# 5_0_1.net
KiCad netlist of a schematic drawn in EasyEDA
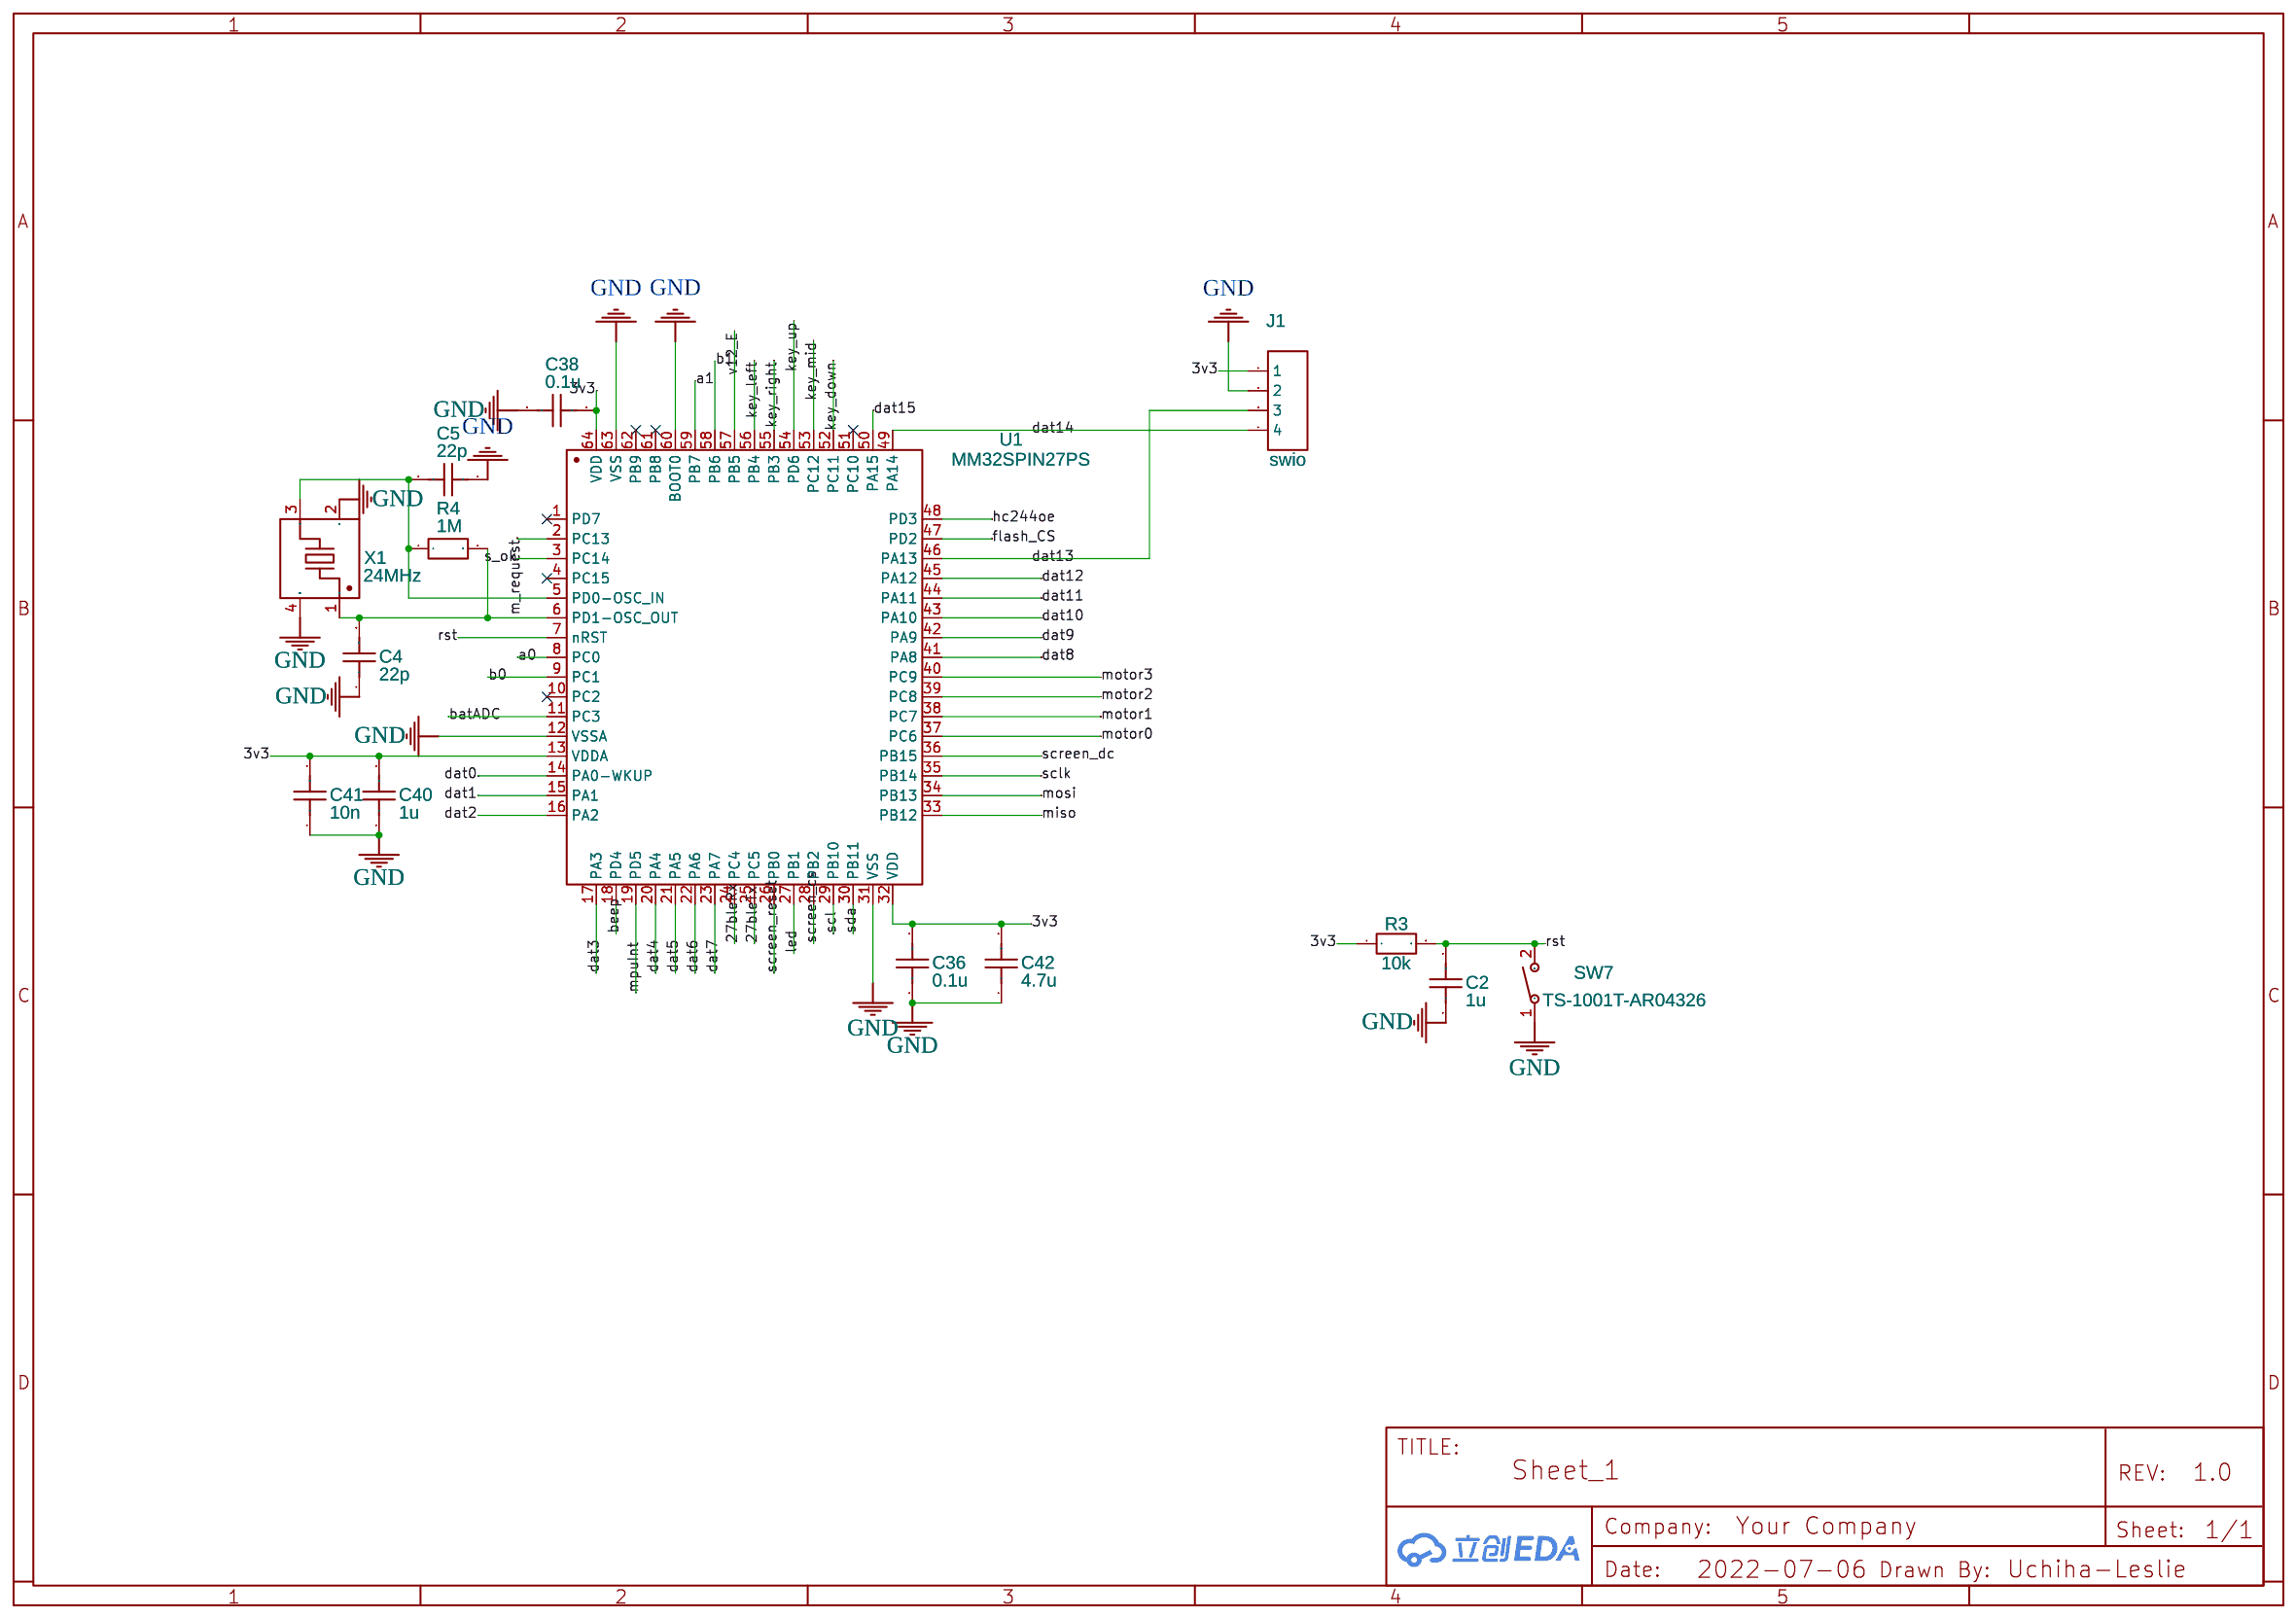
[diagram p0: spin27]
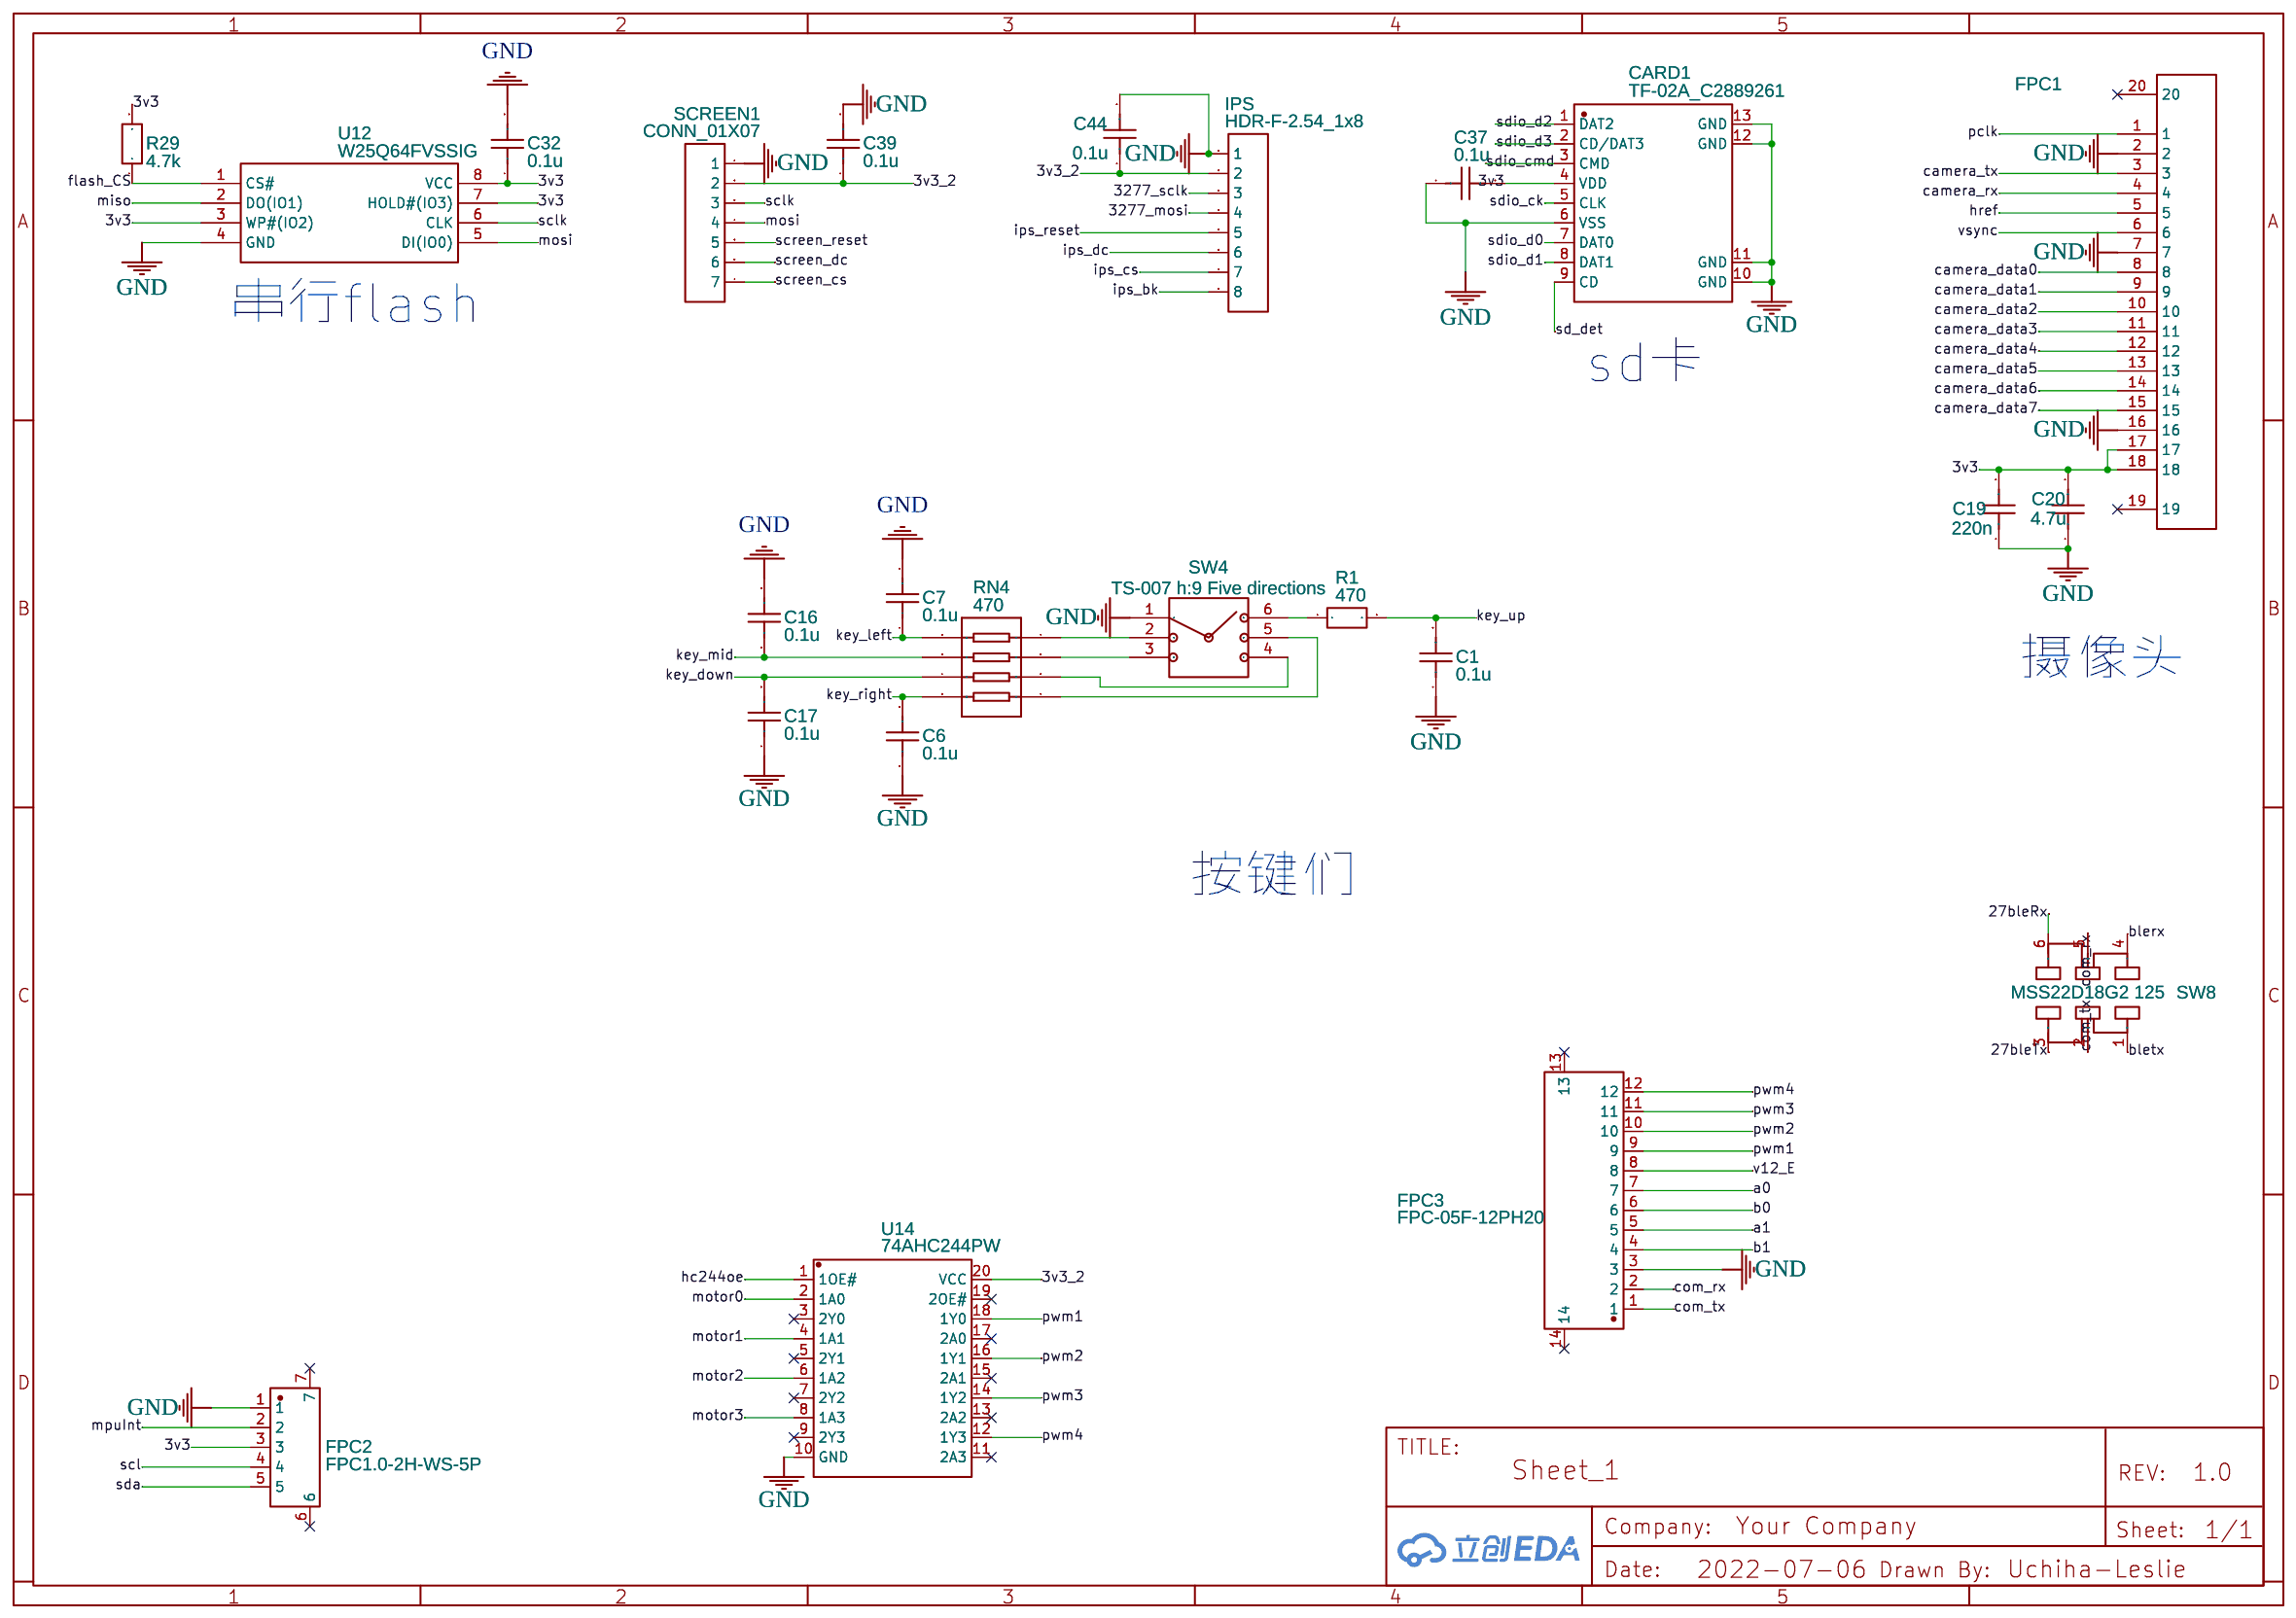
[diagram p1: 其他外设]
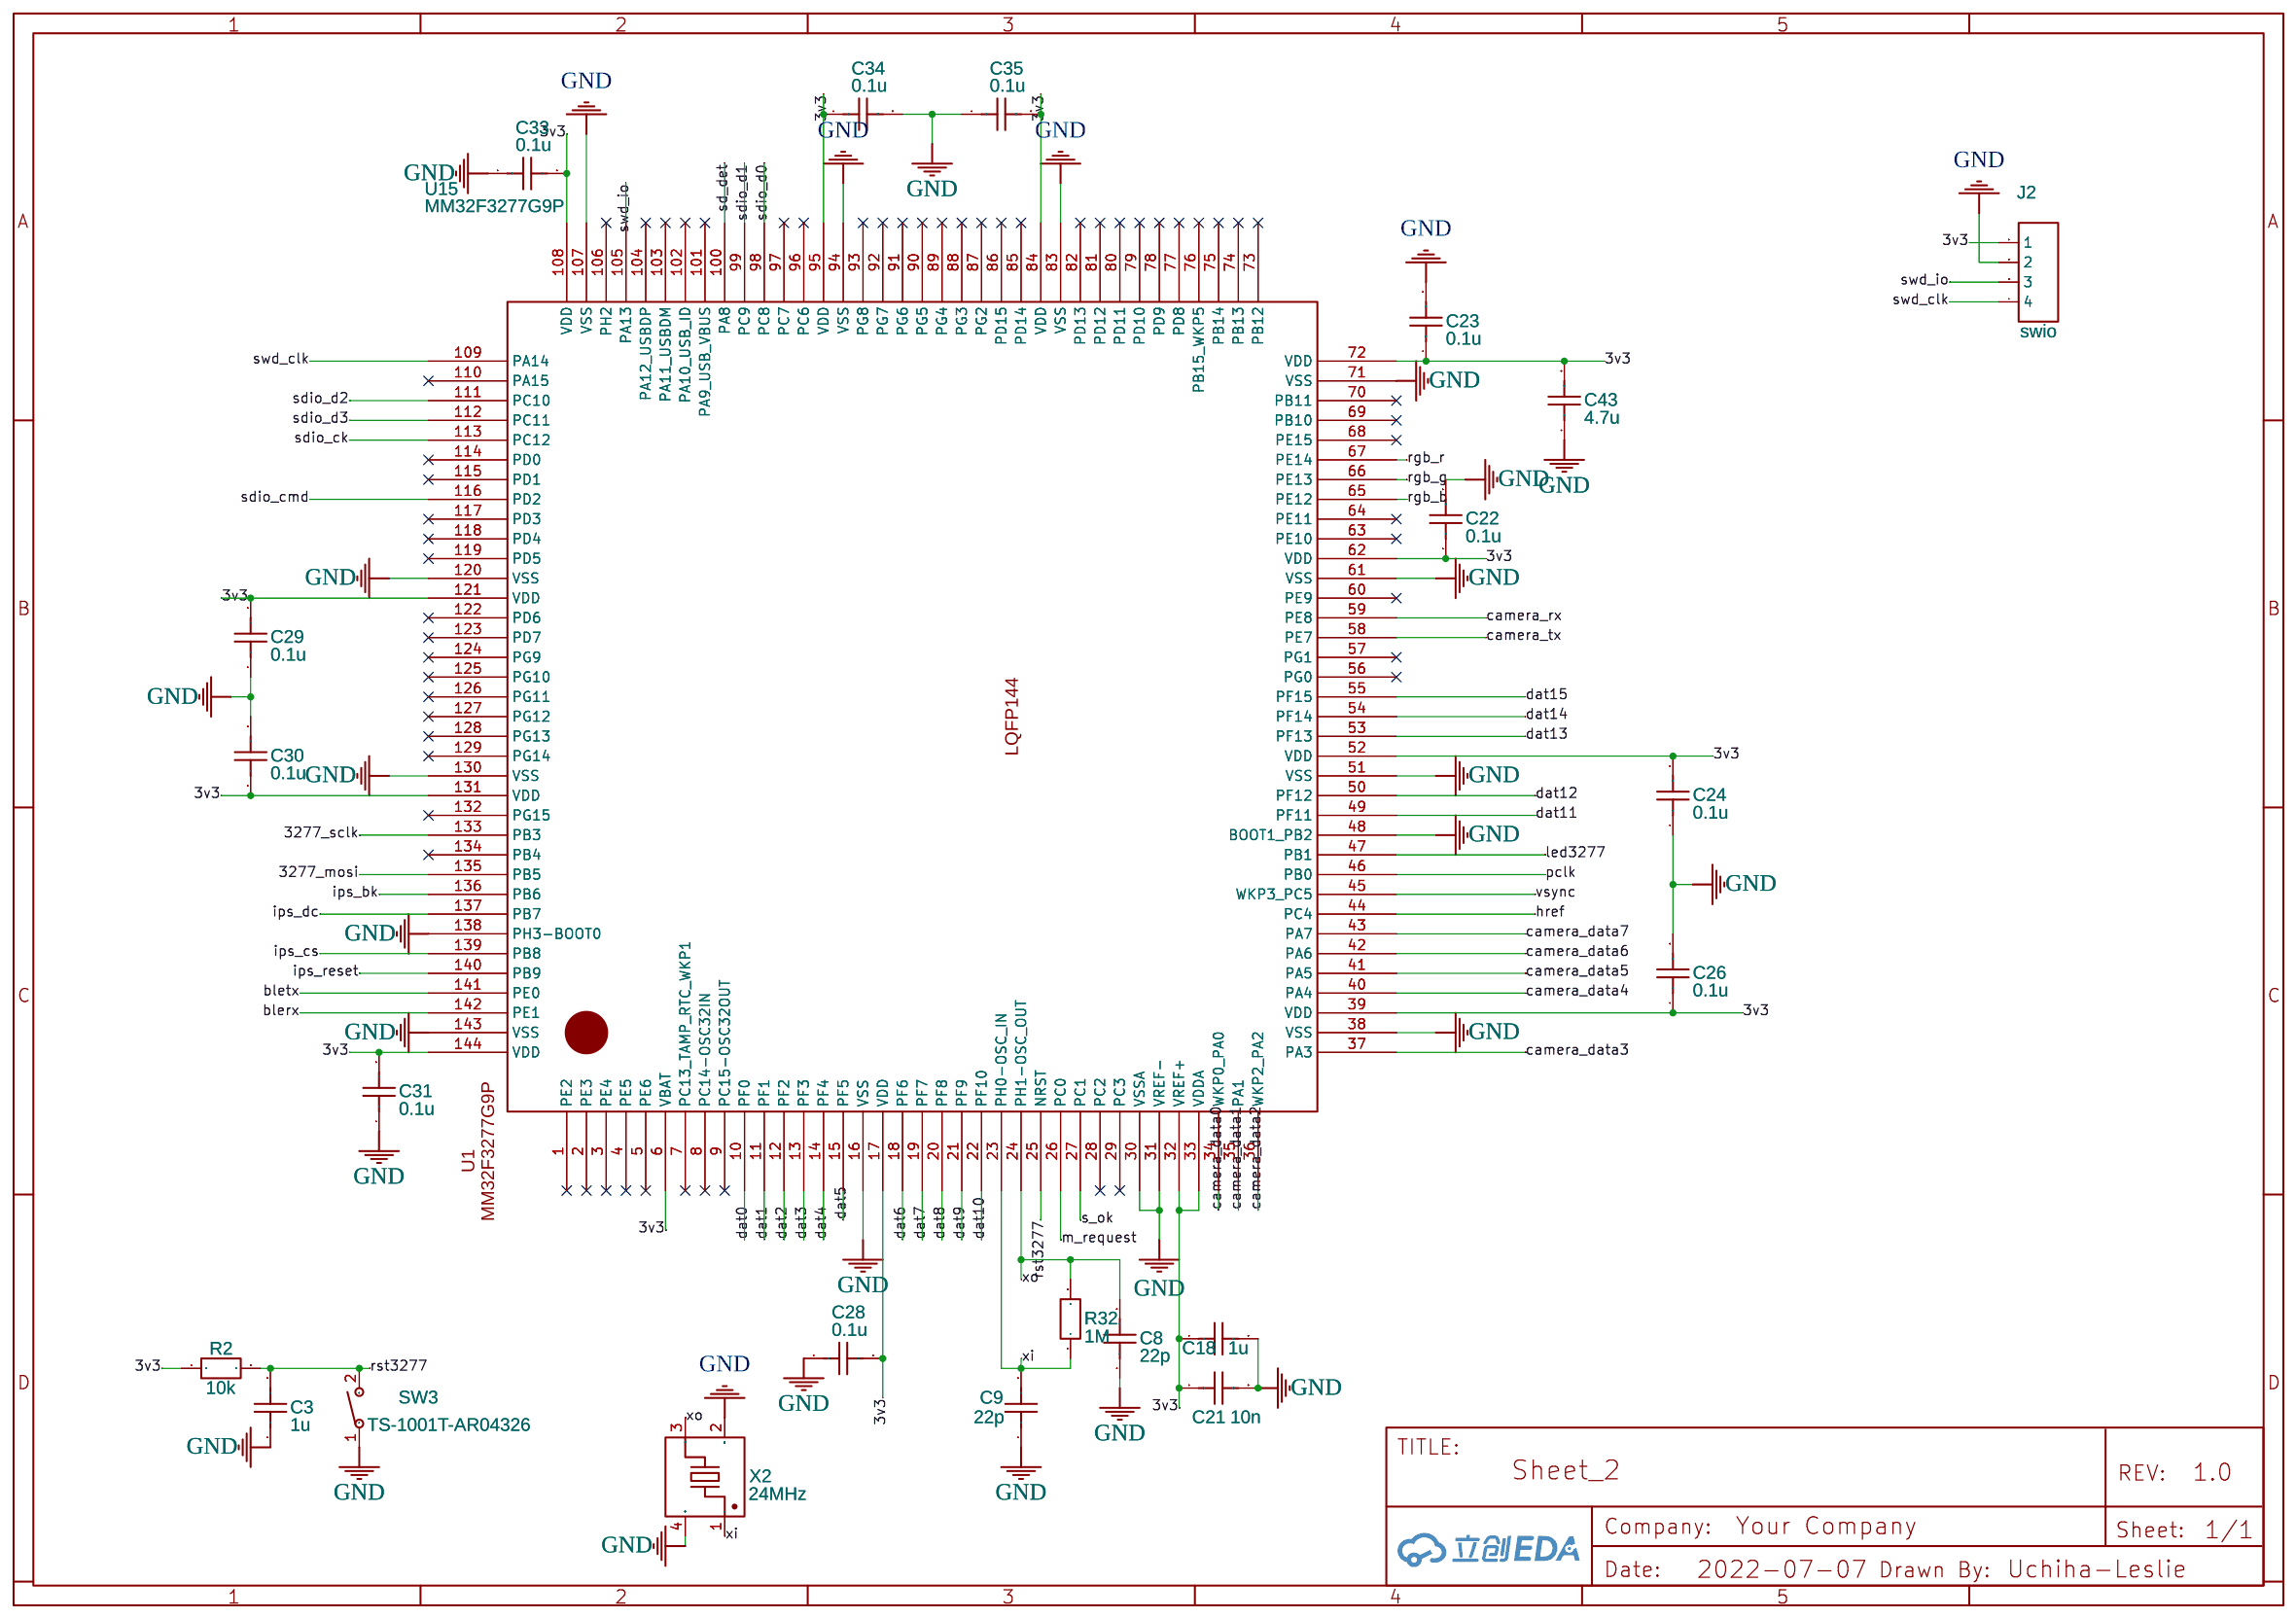
[diagram p2: 3277]
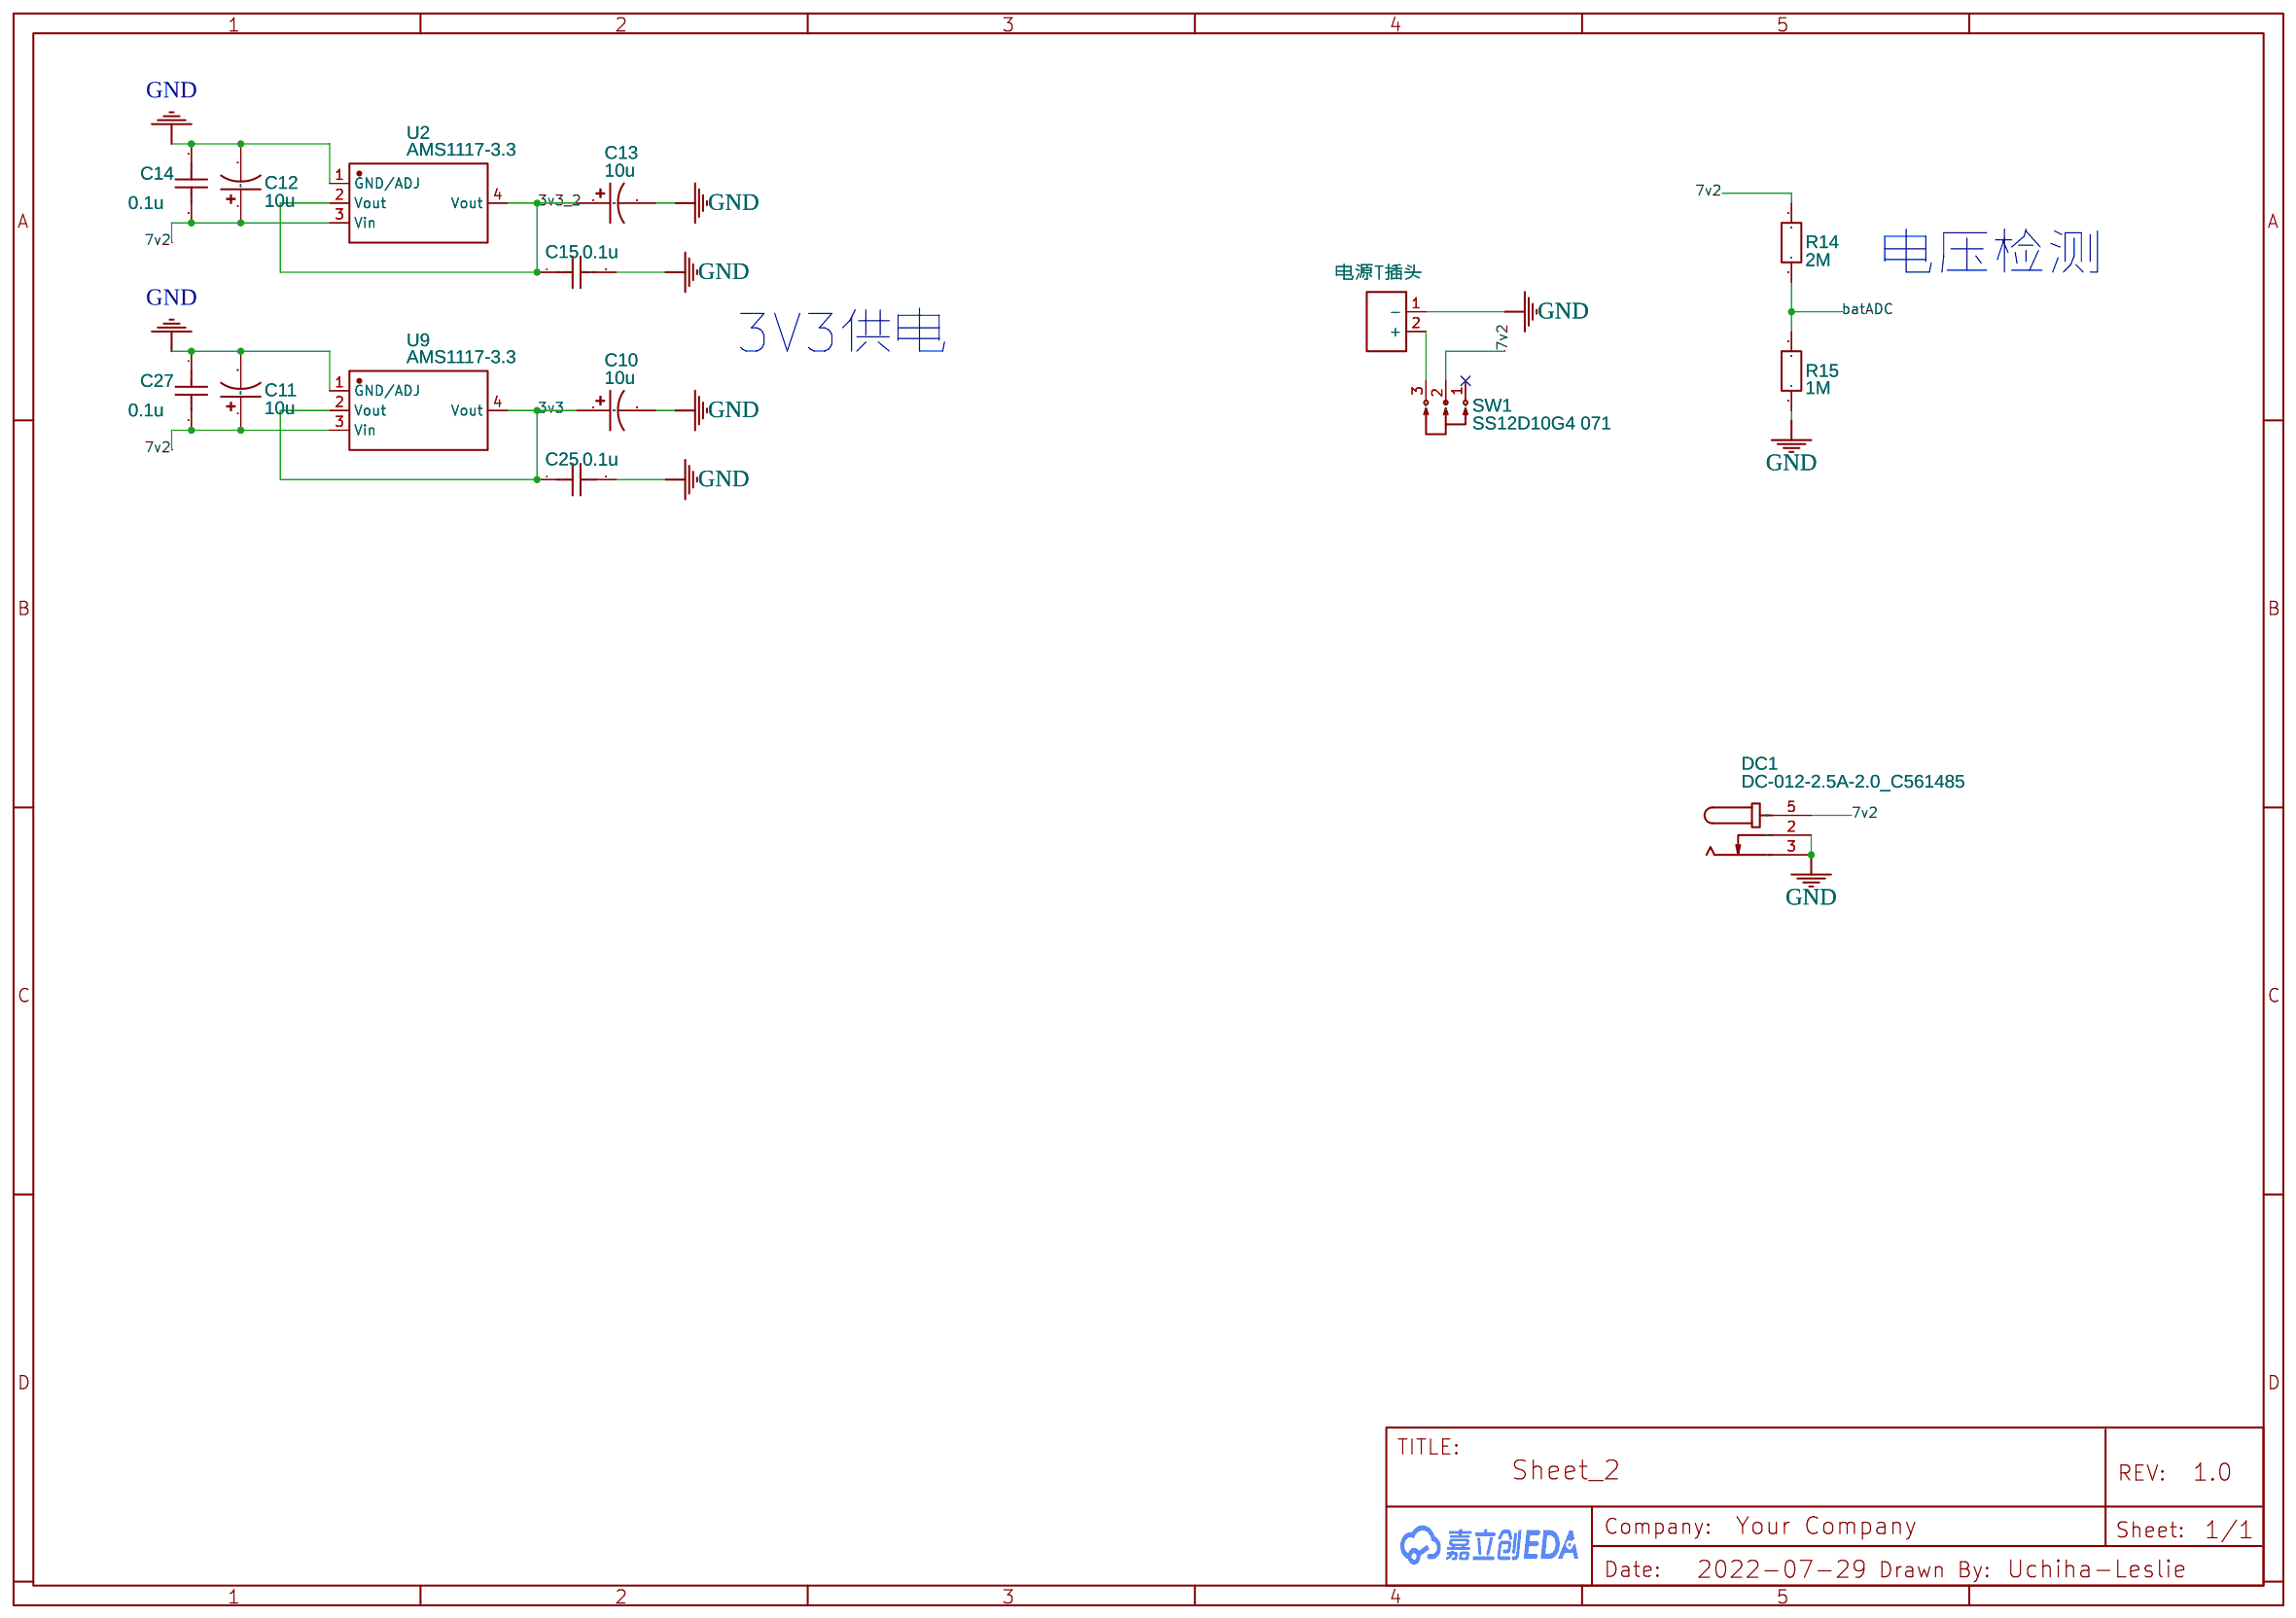
[diagram p3: 电源、稳压与测量]
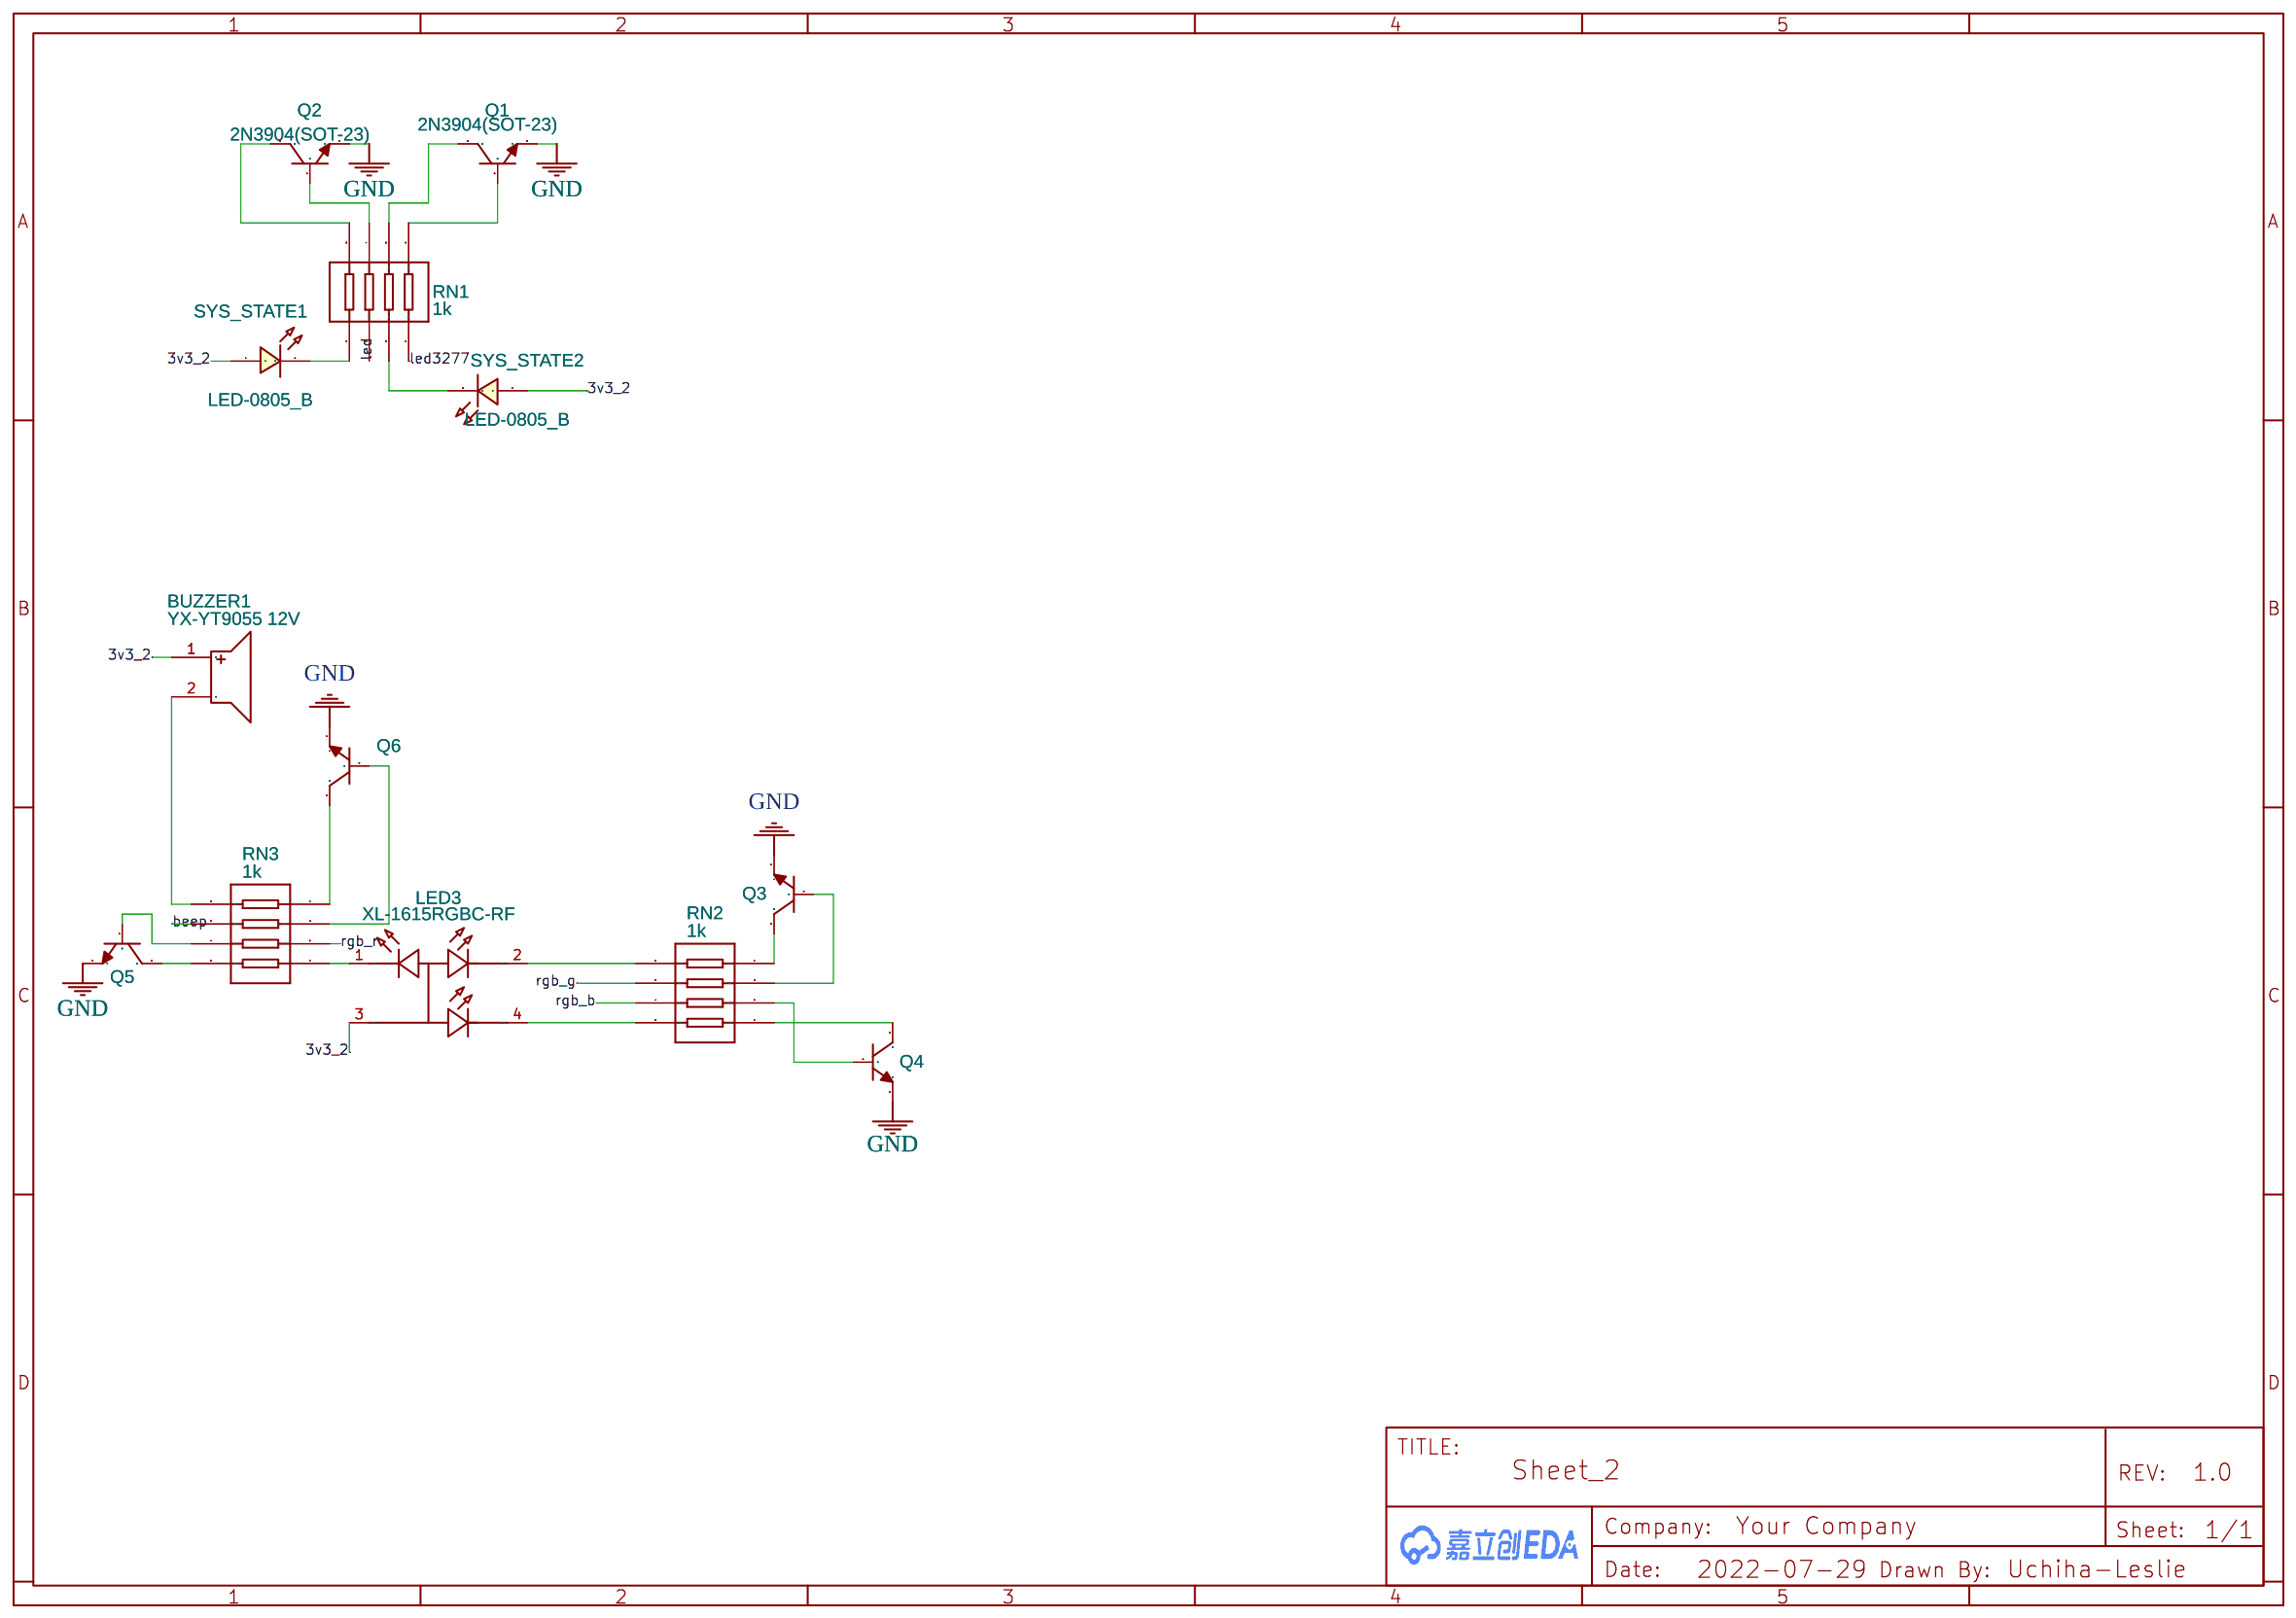
[diagram p4: 蜂鸣器与LED]

(export (version "E")
  (design (tool "Eeschema 10.0.6"))
  (components
    (comp (ref "C2") (value "1u") (libsource (lib "") (part "C_0603_US")))
    (comp (ref "C4") (value "22p") (libsource (lib "") (part "C_0603_US")))
    (comp (ref "C5") (value "22p") (libsource (lib "") (part "C_0603_US_1")))
    (comp (ref "C36") (value "0.1u") (libsource (lib "") (part "C_0402_US")))
    (comp (ref "C38") (value "0.1u") (libsource (lib "") (part "C_0402_US_1")))
    (comp (ref "C40") (value "1u") (libsource (lib "") (part "C_0603_US")))
    (comp (ref "C41") (value "10n") (libsource (lib "") (part "C_0603_US")))
    (comp (ref "C42") (value "4.7u") (libsource (lib "") (part "C_0603_US")))
    (comp (ref "J1")
      (value "swio")
      (fields (field (name "BOM_Supplier Part") "C124378"))
      (libsource (lib "") (part "HDR-M-2.54_1x4"))
    )
    (comp (ref "R3") (value "10k") (libsource (lib "") (part "R_0603_EU")))
    (comp (ref "R4") (value "1M") (libsource (lib "") (part "R_0603_EU")))
    (comp (ref "SW7")
      (value "TS-1001T-AR04326")
      (fields (field (name "BOM_Supplier Part") "C920203"))
      (libsource (lib "") (part "TS-1001T-AR04326"))
    )
    (comp (ref "U1")
      (value "MM32SPIN27PS")
      (fields
        (field (name "BOM_Manufacturer Part") "mm32spin27ps")
        (field (name "BOM_Supplier Part") "C2908053")
      )
      (libsource (lib "") (part "MM32SPIN27PS"))
    )
    (comp (ref "X1")
      (value "24MHz")
      (fields
        (field (name "BOM_Manufacturer Part") "CN4024M00012T8188012")
        (field (name "BOM_Supplier Part") "C708987")
      )
      (libsource (lib "") (part "CN4024M00012T8188012"))
    )
    (comp (ref "C1") (value "0.1u") (libsource (lib "") (part "C_0402_US")))
    (comp (ref "C6") (value "0.1u") (libsource (lib "") (part "C_0402_US")))
    (comp (ref "C7") (value "0.1u") (libsource (lib "") (part "C_0402_US")))
    (comp (ref "C16") (value "0.1u") (libsource (lib "") (part "C_0402_US")))
    (comp (ref "C17") (value "0.1u") (libsource (lib "") (part "C_0402_US")))
    (comp (ref "C19") (value "220n") (libsource (lib "") (part "C_0603_US")))
    (comp (ref "C20") (value "4.7u") (libsource (lib "") (part "C_0603_US")))
    (comp (ref "C32") (value "0.1u") (libsource (lib "") (part "C_0402_US")))
    (comp (ref "C37") (value "0.1u") (libsource (lib "") (part "C_0402_US_1")))
    (comp (ref "C39") (value "0.1u") (libsource (lib "") (part "C_0402_US")))
    (comp (ref "C44") (value "0.1u") (libsource (lib "") (part "C_0402_US")))
    (comp (ref "CARD1")
      (value "TF-02A_C2889261")
      (fields (field (name "BOM_Manufacturer Part") "TF-02A") (field (name "BOM_Supplier Part") "C2889261"))
      (libsource (lib "") (part "TF-02A_C2889261"))
    )
    (comp (ref "FPC1")
      (value "F0500WR-S-18PNLNG1GB0R")
      (fields (field (name "BOM_Supplier Part") "C247896"))
      (libsource (lib "") (part "F0500WR-S-18PNLNG1GB0R"))
    )
    (comp (ref "FPC2")
      (value "FPC1.0-2H-WS-5P")
      (fields (field (name "BOM_Supplier Part") "C9900003417"))
      (libsource (lib "") (part "FPC1.0-2H-WS-5P"))
    )
    (comp (ref "FPC3")
      (value "FPC-05F-12PH20")
      (fields (field (name "BOM_Supplier Part") "C2856799"))
      (libsource (lib "") (part "FPC-05F-12PH20"))
    )
    (comp (ref "IPS")
      (value "HDR-F-2.54_1x8")
      (fields (field (name "BOM_Supplier Part") "C225505"))
      (libsource (lib "") (part "HDR-F-2.54_1x8"))
    )
    (comp (ref "R1") (value "470") (libsource (lib "") (part "R_0603_EU")))
    (comp (ref "R29") (value "4.7k") (libsource (lib "") (part "R_0603_EU_1")))
    (comp (ref "RN4")
      (value "470")
      (fields
        (field (name "BOM_Manufacturer Part") "YC164-JR-070RL")
        (field (name "BOM_Supplier Part") "C327053")
      )
      (libsource (lib "") (part "YC164-JR-070RL"))
    )
    (comp (ref "SCREEN1") (value "CONN_01X07") (libsource (lib "") (part "CONN_01X07")))
    (comp (ref "SW4")
      (value "TS-007 h:9 Five directions")
      (fields (field (name "BOM_Supplier Part") "C3679"))
      (libsource (lib "") (part "TS-007 h{colon}9 Five directions"))
    )
    (comp (ref "SW8")
      (value "MSS22D18G2 125")
      (fields (field (name "BOM_Supplier Part") "C2906278"))
      (libsource (lib "") (part "MSS22D18G2 125"))
    )
    (comp (ref "U12")
      (value "W25Q64FVSSIG")
      (fields (field (name "BOM_Supplier Part") "C14067"))
      (libsource (lib "") (part "W25Q64FVSSIG"))
    )
    (comp (ref "U14")
      (value "74AHC244PW")
      (fields (field (name "BOM_Supplier Part") "C5515"))
      (libsource (lib "") (part "74AHC244PW"))
    )
    (comp (ref "C3") (value "1u") (libsource (lib "") (part "C_0603_US")))
    (comp (ref "C8") (value "22p") (libsource (lib "") (part "C_0603_US")))
    (comp (ref "C9") (value "22p") (libsource (lib "") (part "C_0603_US")))
    (comp (ref "C18") (value "1u") (libsource (lib "") (part "C_0603_US_1")))
    (comp (ref "C21") (value "10n") (libsource (lib "") (part "C_0603_US_1")))
    (comp (ref "C22") (value "0.1u") (libsource (lib "") (part "C_0402_US")))
    (comp (ref "C23") (value "0.1u") (libsource (lib "") (part "C_0402_US")))
    (comp (ref "C24") (value "0.1u") (libsource (lib "") (part "C_0402_US")))
    (comp (ref "C26") (value "0.1u") (libsource (lib "") (part "C_0402_US")))
    (comp (ref "C28") (value "0.1u") (libsource (lib "") (part "C_0402_US_1")))
    (comp (ref "C29") (value "0.1u") (libsource (lib "") (part "C_0402_US")))
    (comp (ref "C30") (value "0.1u") (libsource (lib "") (part "C_0402_US")))
    (comp (ref "C31") (value "0.1u") (libsource (lib "") (part "C_0402_US")))
    (comp (ref "C33") (value "0.1u") (libsource (lib "") (part "C_0402_US_1")))
    (comp (ref "C34") (value "0.1u") (libsource (lib "") (part "C_0402_US_1")))
    (comp (ref "C35") (value "0.1u") (libsource (lib "") (part "C_0402_US_1")))
    (comp (ref "C43") (value "4.7u") (libsource (lib "") (part "C_0603_US")))
    (comp (ref "J2")
      (value "swio")
      (fields (field (name "BOM_Supplier Part") "C124378"))
      (libsource (lib "") (part "HDR-M-2.54_1x4"))
    )
    (comp (ref "R2") (value "10k") (libsource (lib "") (part "R_0603_EU_1")))
    (comp (ref "R32") (value "1M") (libsource (lib "") (part "R_0603_EU")))
    (comp (ref "SW3")
      (value "TS-1001T-AR04326")
      (fields (field (name "BOM_Supplier Part") "C920203"))
      (libsource (lib "") (part "TS-1001T-AR04326"))
    )
    (comp (ref "U15") (value "MM32F3277G9P") (libsource (lib "") (part "MM32F3277G9P")))
    (comp (ref "X2")
      (value "24MHz")
      (fields
        (field (name "BOM_Manufacturer Part") "CN4024M00012T8188012")
        (field (name "BOM_Supplier Part") "C708987")
      )
      (libsource (lib "") (part "CN4024M00012T8188012"))
    )
    (comp (ref "C10") (value "10u") (libsource (lib "") (part "C_Tan_SMD_A_US")))
    (comp (ref "C11") (value "10u") (libsource (lib "") (part "C_Tan_SMD_A_US_1")))
    (comp (ref "C12") (value "10u") (libsource (lib "") (part "C_Tan_SMD_A_US_1")))
    (comp (ref "C13") (value "10u") (libsource (lib "") (part "C_Tan_SMD_A_US")))
    (comp (ref "C14") (value "0.1u") (libsource (lib "") (part "C_0603_US_1")))
    (comp (ref "C15") (value "0.1u") (libsource (lib "") (part "C_0603_US")))
    (comp (ref "C25") (value "0.1u") (libsource (lib "") (part "C_0603_US")))
    (comp (ref "C27") (value "0.1u") (libsource (lib "") (part "C_0603_US_1")))
    (comp (ref "DC1")
      (value "DC-012-2.5A-2.0_C561485")
      (fields
        (field (name "BOM_Manufacturer Part") "DC-012-2.5A-2.0")
        (field (name "BOM_Supplier Part") "C561485")
      )
      (libsource (lib "") (part "DC-012-2.5A-2.0_C561485"))
    )
    (comp (ref "H1")
      (value "电源T插头")
      (fields (field (name "BOM_Manufacturer Part") "3-644456-2") (field (name "BOM_Supplier Part") "C90288"))
      (libsource (lib "") (part "电源T插头"))
    )
    (comp (ref "R14") (value "2M") (libsource (lib "") (part "R_0603_EU")))
    (comp (ref "R15") (value "1M") (libsource (lib "") (part "R_0603_EU")))
    (comp (ref "SW1")
      (value "SS12D10G4 071")
      (fields (field (name "BOM_Supplier Part") "C2887259"))
      (libsource (lib "") (part "SS12D10G4 071"))
    )
    (comp (ref "U2")
      (value "AMS1117-3.3")
      (fields (field (name "BOM_Supplier Part") "C6186"))
      (libsource (lib "") (part "AMS1117-3.3"))
    )
    (comp (ref "U9")
      (value "AMS1117-3.3")
      (fields (field (name "BOM_Supplier Part") "C6186"))
      (libsource (lib "") (part "AMS1117-3.3"))
    )
    (comp (ref "BUZZER1")
      (value "YX-YT9055 12V")
      (fields (field (name "BOM_Supplier Part") "C781852"))
      (libsource (lib "") (part "YX-YT9055 12V"))
    )
    (comp (ref "LED3")
      (value "XL-1615RGBC-RF")
      (fields (field (name "BOM_Supplier Part") "C965840"))
      (libsource (lib "") (part "XL-1615RGBC-RF"))
    )
    (comp (ref "Q1")
      (value "2N3904(SOT-23)")
      (fields
        (field (name "BOM_Manufacturer Part") "2n3904S-RTK/PS")
        (field (name "BOM_Supplier Part") "C18536")
      )
      (libsource (lib "") (part "2N3904(SOT-23)_1"))
    )
    (comp (ref "Q2")
      (value "2N3904(SOT-23)")
      (fields
        (field (name "BOM_Manufacturer Part") "2n3904S-RTK/PS")
        (field (name "BOM_Supplier Part") "C18536")
      )
      (libsource (lib "") (part "2N3904(SOT-23)_1"))
    )
    (comp (ref "Q3")
      (value "2N3904(SOT-23)")
      (fields
        (field (name "BOM_Manufacturer Part") "2n3904S-RTK/PS")
        (field (name "BOM_Supplier Part") "C18536")
      )
      (libsource (lib "") (part "2N3904(SOT-23)"))
    )
    (comp (ref "Q4")
      (value "2N3904(SOT-23)")
      (fields
        (field (name "BOM_Manufacturer Part") "2n3904S-RTK/PS")
        (field (name "BOM_Supplier Part") "C18536")
      )
      (libsource (lib "") (part "2N3904(SOT-23)_2"))
    )
    (comp (ref "Q5")
      (value "2N3904(SOT-23)")
      (fields
        (field (name "BOM_Manufacturer Part") "2n3904S-RTK/PS")
        (field (name "BOM_Supplier Part") "C18536")
      )
      (libsource (lib "") (part "2N3904(SOT-23)_3"))
    )
    (comp (ref "Q6")
      (value "2N3904(SOT-23)")
      (fields
        (field (name "BOM_Manufacturer Part") "2n3904S-RTK/PS")
        (field (name "BOM_Supplier Part") "C18536")
      )
      (libsource (lib "") (part "2N3904(SOT-23)"))
    )
    (comp (ref "RN1")
      (value "1k")
      (fields
        (field (name "BOM_Manufacturer Part") "YC164-JR-070RL")
        (field (name "BOM_Supplier Part") "C327053")
      )
      (libsource (lib "") (part "YC164-JR-070RL"))
    )
    (comp (ref "RN2")
      (value "1k")
      (fields
        (field (name "BOM_Manufacturer Part") "YC164-JR-070RL")
        (field (name "BOM_Supplier Part") "C327053")
      )
      (libsource (lib "") (part "YC164-JR-070RL_1"))
    )
    (comp (ref "RN3")
      (value "1k")
      (fields
        (field (name "BOM_Manufacturer Part") "YC164-JR-070RL")
        (field (name "BOM_Supplier Part") "C327053")
      )
      (libsource (lib "") (part "YC164-JR-070RL_1"))
    )
    (comp (ref "SYS_STATE1")
      (value "LED-0805_B")
      (fields
        (field (name "BOM_Manufacturer Part") "D-B080508B1-KS2")
        (field (name "BOM_Supplier Part") "C108412")
      )
      (libsource (lib "") (part "LED-0805_B"))
    )
    (comp (ref "SYS_STATE2")
      (value "LED-0805_B")
      (fields
        (field (name "BOM_Manufacturer Part") "D-B080508B1-KS2")
        (field (name "BOM_Supplier Part") "C108412")
      )
      (libsource (lib "") (part "LED-0805_B_1"))
    )
  )
  (nets
    (net (code "1") (name "3v3") (class "Default")
      (node (ref "C10") (pin "1") (pinfunction "1_1") (pintype "unspecified"))
      (node (ref "C18") (pin "1") (pinfunction "1_1") (pintype "unspecified"))
      (node (ref "C19") (pin "2") (pinfunction "2_2") (pintype "unspecified"))
      (node (ref "C20") (pin "2") (pinfunction "2_2") (pintype "unspecified"))
      (node (ref "C21") (pin "1") (pinfunction "1_1") (pintype "unspecified"))
      (node (ref "C22") (pin "1") (pinfunction "1_1") (pintype "unspecified"))
      (node (ref "C23") (pin "1") (pinfunction "1_1") (pintype "unspecified"))
      (node (ref "C24") (pin "2") (pinfunction "2_2") (pintype "unspecified"))
      (node (ref "C25") (pin "1") (pinfunction "1_1") (pintype "unspecified"))
      (node (ref "C26") (pin "1") (pinfunction "1_1") (pintype "unspecified"))
      (node (ref "C28") (pin "2") (pinfunction "2_2") (pintype "unspecified"))
      (node (ref "C29") (pin "2") (pinfunction "2_2") (pintype "unspecified"))
      (node (ref "C30") (pin "1") (pinfunction "1_1") (pintype "unspecified"))
      (node (ref "C31") (pin "2") (pinfunction "2_2") (pintype "unspecified"))
      (node (ref "C32") (pin "1") (pinfunction "1_1") (pintype "unspecified"))
      (node (ref "C33") (pin "2") (pinfunction "2_2") (pintype "unspecified"))
      (node (ref "C34") (pin "1") (pinfunction "1_1") (pintype "unspecified"))
      (node (ref "C35") (pin "2") (pinfunction "2_2") (pintype "unspecified"))
      (node (ref "C36") (pin "2") (pinfunction "2_2") (pintype "unspecified"))
      (node (ref "C37") (pin "2") (pinfunction "2_2") (pintype "unspecified"))
      (node (ref "C38") (pin "2") (pinfunction "2_2") (pintype "unspecified"))
      (node (ref "C40") (pin "2") (pinfunction "2_2") (pintype "unspecified"))
      (node (ref "C41") (pin "2") (pinfunction "2_2") (pintype "unspecified"))
      (node (ref "C42") (pin "2") (pinfunction "2_2") (pintype "unspecified"))
      (node (ref "C43") (pin "2") (pinfunction "2_2") (pintype "unspecified"))
      (node (ref "CARD1") (pin "4") (pinfunction "VDD_4") (pintype "unspecified"))
      (node (ref "FPC1") (pin "17") (pinfunction "17_17") (pintype "unspecified"))
      (node (ref "FPC1") (pin "18") (pinfunction "18_18") (pintype "unspecified"))
      (node (ref "FPC2") (pin "3") (pinfunction "3_3") (pintype "unspecified"))
      (node (ref "J1") (pin "1") (pinfunction "1_1") (pintype "unspecified"))
      (node (ref "J2") (pin "1") (pinfunction "1_1") (pintype "unspecified"))
      (node (ref "R2") (pin "1") (pinfunction "1_1") (pintype "unspecified"))
      (node (ref "R29") (pin "2") (pinfunction "2_2") (pintype "unspecified"))
      (node (ref "R3") (pin "1") (pinfunction "1_1") (pintype "unspecified"))
      (node (ref "U1") (pin "13") (pinfunction "VDDA_13") (pintype "unspecified"))
      (node (ref "U1") (pin "32") (pinfunction "VDD_32") (pintype "unspecified"))
      (node (ref "U1") (pin "64") (pinfunction "VDD_64") (pintype "unspecified"))
      (node (ref "U12") (pin "3") (pinfunction "WP#(IO2)_3") (pintype "unspecified"))
      (node (ref "U12") (pin "7") (pinfunction "HOLD#(IO3)_7") (pintype "unspecified"))
      (node (ref "U12") (pin "8") (pinfunction "VCC_8") (pintype "unspecified"))
      (node (ref "U15") (pin "108") (pinfunction "VDD_108") (pintype "unspecified"))
      (node (ref "U15") (pin "121") (pinfunction "VDD_121") (pintype "unspecified"))
      (node (ref "U15") (pin "131") (pinfunction "VDD_131") (pintype "unspecified"))
      (node (ref "U15") (pin "144") (pinfunction "VDD_144") (pintype "unspecified"))
      (node (ref "U15") (pin "17") (pinfunction "VDD_17") (pintype "unspecified"))
      (node (ref "U15") (pin "32") (pinfunction "VREF+_32") (pintype "unspecified"))
      (node (ref "U15") (pin "33") (pinfunction "VDDA_33") (pintype "unspecified"))
      (node (ref "U15") (pin "39") (pinfunction "VDD_39") (pintype "unspecified"))
      (node (ref "U15") (pin "52") (pinfunction "VDD_52") (pintype "unspecified"))
      (node (ref "U15") (pin "6") (pinfunction "VBAT_6") (pintype "unspecified"))
      (node (ref "U15") (pin "62") (pinfunction "VDD_62") (pintype "unspecified"))
      (node (ref "U15") (pin "72") (pinfunction "VDD_72") (pintype "unspecified"))
      (node (ref "U15") (pin "84") (pinfunction "VDD_84") (pintype "unspecified"))
      (node (ref "U15") (pin "95") (pinfunction "VDD_95") (pintype "unspecified"))
      (node (ref "U9") (pin "2") (pinfunction "Vout_2") (pintype "unspecified"))
      (node (ref "U9") (pin "4") (pinfunction "Vout_4") (pintype "unspecified"))
    )
    (net (code "2") (name "3v3_2") (class "Default")
      (node (ref "BUZZER1") (pin "1") (pinfunction "1_1") (pintype "unspecified"))
      (node (ref "C13") (pin "1") (pinfunction "1_1") (pintype "unspecified"))
      (node (ref "C15") (pin "1") (pinfunction "1_1") (pintype "unspecified"))
      (node (ref "C39") (pin "1") (pinfunction "1_1") (pintype "unspecified"))
      (node (ref "C44") (pin "1") (pinfunction "1_1") (pintype "unspecified"))
      (node (ref "IPS") (pin "2") (pinfunction "2_2") (pintype "unspecified"))
      (node (ref "LED3") (pin "3") (pinfunction "COM+_3") (pintype "unspecified"))
      (node (ref "SCREEN1") (pin "2") (pinfunction "2_2") (pintype "input"))
      (node (ref "SYS_STATE1") (pin "1") (pinfunction "1_1") (pintype "unspecified"))
      (node (ref "SYS_STATE2") (pin "1") (pinfunction "1_1") (pintype "unspecified"))
      (node (ref "U14") (pin "20") (pinfunction "VCC_20") (pintype "unspecified"))
      (node (ref "U2") (pin "2") (pinfunction "Vout_2") (pintype "unspecified"))
      (node (ref "U2") (pin "4") (pinfunction "Vout_4") (pintype "unspecified"))
    )
    (net (code "3") (name "7v2") (class "Default")
      (node (ref "C11") (pin "1") (pinfunction "1_1") (pintype "unspecified"))
      (node (ref "C12") (pin "1") (pinfunction "1_1") (pintype "unspecified"))
      (node (ref "C14") (pin "2") (pinfunction "2_2") (pintype "unspecified"))
      (node (ref "C27") (pin "2") (pinfunction "2_2") (pintype "unspecified"))
      (node (ref "DC1") (pin "5") (pinfunction "5_5") (pintype "unspecified"))
      (node (ref "R14") (pin "2") (pinfunction "2_2") (pintype "unspecified"))
      (node (ref "SW1") (pin "2") (pinfunction "2_2") (pintype "unspecified"))
      (node (ref "U2") (pin "3") (pinfunction "Vin_3") (pintype "unspecified"))
      (node (ref "U9") (pin "3") (pinfunction "Vin_3") (pintype "unspecified"))
    )
    (net (code "4") (name "27bleRx") (class "Default")
      (node (ref "SW8") (pin "6") (pinfunction "6_6") (pintype "unspecified"))
      (node (ref "U1") (pin "24") (pinfunction "PC4_24") (pintype "unspecified"))
    )
    (net (code "5") (name "27bleTx") (class "Default")
      (node (ref "SW8") (pin "3") (pinfunction "3_3") (pintype "unspecified"))
      (node (ref "U1") (pin "25") (pinfunction "PC5_25") (pintype "unspecified"))
    )
    (net (code "6") (name "3277_mosi") (class "Default")
      (node (ref "IPS") (pin "4") (pinfunction "4_4") (pintype "unspecified"))
      (node (ref "U15") (pin "135") (pinfunction "PB5_135") (pintype "unspecified"))
    )
    (net (code "7") (name "3277_sclk") (class "Default")
      (node (ref "IPS") (pin "3") (pinfunction "3_3") (pintype "unspecified"))
      (node (ref "U15") (pin "133") (pinfunction "PB3_133") (pintype "unspecified"))
    )
    (net (code "8") (name "GND") (class "Default")
      (node (ref "C1") (pin "1") (pinfunction "1_1") (pintype "unspecified"))
      (node (ref "C10") (pin "2") (pinfunction "2_2") (pintype "unspecified"))
      (node (ref "C11") (pin "2") (pinfunction "2_2") (pintype "unspecified"))
      (node (ref "C12") (pin "2") (pinfunction "2_2") (pintype "unspecified"))
      (node (ref "C13") (pin "2") (pinfunction "2_2") (pintype "unspecified"))
      (node (ref "C14") (pin "1") (pinfunction "1_1") (pintype "unspecified"))
      (node (ref "C15") (pin "2") (pinfunction "2_2") (pintype "unspecified"))
      (node (ref "C16") (pin "2") (pinfunction "2_2") (pintype "unspecified"))
      (node (ref "C17") (pin "1") (pinfunction "1_1") (pintype "unspecified"))
      (node (ref "C18") (pin "2") (pinfunction "2_2") (pintype "unspecified"))
      (node (ref "C19") (pin "1") (pinfunction "1_1") (pintype "unspecified"))
      (node (ref "C2") (pin "1") (pinfunction "1_1") (pintype "unspecified"))
      (node (ref "C20") (pin "1") (pinfunction "1_1") (pintype "unspecified"))
      (node (ref "C21") (pin "2") (pinfunction "2_2") (pintype "unspecified"))
      (node (ref "C22") (pin "2") (pinfunction "2_2") (pintype "unspecified"))
      (node (ref "C23") (pin "2") (pinfunction "2_2") (pintype "unspecified"))
      (node (ref "C24") (pin "1") (pinfunction "1_1") (pintype "unspecified"))
      (node (ref "C25") (pin "2") (pinfunction "2_2") (pintype "unspecified"))
      (node (ref "C26") (pin "2") (pinfunction "2_2") (pintype "unspecified"))
      (node (ref "C27") (pin "1") (pinfunction "1_1") (pintype "unspecified"))
      (node (ref "C28") (pin "1") (pinfunction "1_1") (pintype "unspecified"))
      (node (ref "C29") (pin "1") (pinfunction "1_1") (pintype "unspecified"))
      (node (ref "C3") (pin "1") (pinfunction "1_1") (pintype "unspecified"))
      (node (ref "C30") (pin "2") (pinfunction "2_2") (pintype "unspecified"))
      (node (ref "C31") (pin "1") (pinfunction "1_1") (pintype "unspecified"))
      (node (ref "C32") (pin "2") (pinfunction "2_2") (pintype "unspecified"))
      (node (ref "C33") (pin "1") (pinfunction "1_1") (pintype "unspecified"))
      (node (ref "C34") (pin "2") (pinfunction "2_2") (pintype "unspecified"))
      (node (ref "C35") (pin "1") (pinfunction "1_1") (pintype "unspecified"))
      (node (ref "C36") (pin "1") (pinfunction "1_1") (pintype "unspecified"))
      (node (ref "C37") (pin "1") (pinfunction "1_1") (pintype "unspecified"))
      (node (ref "C38") (pin "1") (pinfunction "1_1") (pintype "unspecified"))
      (node (ref "C39") (pin "2") (pinfunction "2_2") (pintype "unspecified"))
      (node (ref "C4") (pin "1") (pinfunction "1_1") (pintype "unspecified"))
      (node (ref "C40") (pin "1") (pinfunction "1_1") (pintype "unspecified"))
      (node (ref "C41") (pin "1") (pinfunction "1_1") (pintype "unspecified"))
      (node (ref "C42") (pin "1") (pinfunction "1_1") (pintype "unspecified"))
      (node (ref "C43") (pin "1") (pinfunction "1_1") (pintype "unspecified"))
      (node (ref "C44") (pin "2") (pinfunction "2_2") (pintype "unspecified"))
      (node (ref "C5") (pin "1") (pinfunction "1_1") (pintype "unspecified"))
      (node (ref "C6") (pin "1") (pinfunction "1_1") (pintype "unspecified"))
      (node (ref "C7") (pin "2") (pinfunction "2_2") (pintype "unspecified"))
      (node (ref "C8") (pin "1") (pinfunction "1_1") (pintype "unspecified"))
      (node (ref "C9") (pin "1") (pinfunction "1_1") (pintype "unspecified"))
      (node (ref "CARD1") (pin "10") (pinfunction "GND_10") (pintype "unspecified"))
      (node (ref "CARD1") (pin "11") (pinfunction "GND_11") (pintype "unspecified"))
      (node (ref "CARD1") (pin "12") (pinfunction "GND_12") (pintype "unspecified"))
      (node (ref "CARD1") (pin "13") (pinfunction "GND_13") (pintype "unspecified"))
      (node (ref "CARD1") (pin "6") (pinfunction "VSS_6") (pintype "unspecified"))
      (node (ref "DC1") (pin "2") (pinfunction "2_2") (pintype "unspecified"))
      (node (ref "DC1") (pin "3") (pinfunction "3_3") (pintype "unspecified"))
      (node (ref "FPC1") (pin "16") (pinfunction "16_16") (pintype "unspecified"))
      (node (ref "FPC1") (pin "2") (pinfunction "2_2") (pintype "unspecified"))
      (node (ref "FPC1") (pin "7") (pinfunction "7_7") (pintype "unspecified"))
      (node (ref "FPC2") (pin "1") (pinfunction "1_1") (pintype "unspecified"))
      (node (ref "FPC3") (pin "3") (pinfunction "3_3") (pintype "unspecified"))
      (node (ref "H1") (pin "1") (pinfunction "-_1") (pintype "unspecified"))
      (node (ref "IPS") (pin "1") (pinfunction "1_1") (pintype "unspecified"))
      (node (ref "J1") (pin "2") (pinfunction "2_2") (pintype "unspecified"))
      (node (ref "J2") (pin "2") (pinfunction "2_2") (pintype "unspecified"))
      (node (ref "Q1") (pin "1") (pinfunction "E_1") (pintype "input"))
      (node (ref "Q2") (pin "1") (pinfunction "E_1") (pintype "input"))
      (node (ref "Q3") (pin "1") (pinfunction "E_1") (pintype "input"))
      (node (ref "Q4") (pin "1") (pinfunction "E_1") (pintype "input"))
      (node (ref "Q5") (pin "1") (pinfunction "E_1") (pintype "input"))
      (node (ref "Q6") (pin "1") (pinfunction "E_1") (pintype "input"))
      (node (ref "R15") (pin "1") (pinfunction "1_1") (pintype "unspecified"))
      (node (ref "SCREEN1") (pin "1") (pinfunction "1_1") (pintype "input"))
      (node (ref "SW3") (pin "1") (pinfunction "1_1") (pintype "unspecified"))
      (node (ref "SW4") (pin "1") (pinfunction "1_1") (pintype "input"))
      (node (ref "SW7") (pin "1") (pinfunction "1_1") (pintype "unspecified"))
      (node (ref "U1") (pin "12") (pinfunction "VSSA_12") (pintype "unspecified"))
      (node (ref "U1") (pin "31") (pinfunction "VSS_31") (pintype "unspecified"))
      (node (ref "U1") (pin "60") (pinfunction "BOOT0_60") (pintype "unspecified"))
      (node (ref "U1") (pin "63") (pinfunction "VSS_63") (pintype "unspecified"))
      (node (ref "U12") (pin "4") (pinfunction "GND_4") (pintype "unspecified"))
      (node (ref "U14") (pin "10") (pinfunction "GND_10") (pintype "unspecified"))
      (node (ref "U15") (pin "107") (pinfunction "VSS_107") (pintype "unspecified"))
      (node (ref "U15") (pin "120") (pinfunction "VSS_120") (pintype "unspecified"))
      (node (ref "U15") (pin "130") (pinfunction "VSS_130") (pintype "unspecified"))
      (node (ref "U15") (pin "138") (pinfunction "PH3-BOOT0_138") (pintype "unspecified"))
      (node (ref "U15") (pin "143") (pinfunction "VSS_143") (pintype "unspecified"))
      (node (ref "U15") (pin "16") (pinfunction "VSS_16") (pintype "unspecified"))
      (node (ref "U15") (pin "30") (pinfunction "VSSA_30") (pintype "unspecified"))
      (node (ref "U15") (pin "31") (pinfunction "VREF-_31") (pintype "unspecified"))
      (node (ref "U15") (pin "38") (pinfunction "VSS_38") (pintype "unspecified"))
      (node (ref "U15") (pin "48") (pinfunction "BOOT1_PB2_48") (pintype "unspecified"))
      (node (ref "U15") (pin "51") (pinfunction "VSS_51") (pintype "unspecified"))
      (node (ref "U15") (pin "61") (pinfunction "VSS_61") (pintype "unspecified"))
      (node (ref "U15") (pin "71") (pinfunction "VSS_71") (pintype "unspecified"))
      (node (ref "U15") (pin "83") (pinfunction "VSS_83") (pintype "unspecified"))
      (node (ref "U15") (pin "94") (pinfunction "VSS_94") (pintype "unspecified"))
      (node (ref "U2") (pin "1") (pinfunction "GND/ADJ_1") (pintype "unspecified"))
      (node (ref "U9") (pin "1") (pinfunction "GND/ADJ_1") (pintype "unspecified"))
      (node (ref "X1") (pin "2") (pinfunction "GND_2") (pintype "input"))
      (node (ref "X1") (pin "4") (pinfunction "GND_4") (pintype "input"))
      (node (ref "X2") (pin "2") (pinfunction "GND_2") (pintype "input"))
      (node (ref "X2") (pin "4") (pinfunction "GND_4") (pintype "input"))
    )
    (net (code "9") (name "Net-(BUZZER1-Pad2)") (class "Default")
      (node (ref "BUZZER1") (pin "2") (pinfunction "2_2") (pintype "unspecified"))
      (node (ref "RN3") (pin "5") (pinfunction "5_5") (pintype "input"))
    )
    (net (code "10") (name "Net-(H1-+)") (class "Default")
      (node (ref "H1") (pin "2") (pinfunction "+_2") (pintype "unspecified"))
      (node (ref "SW1") (pin "3") (pinfunction "3_3") (pintype "unspecified"))
    )
    (net (code "11") (name "Net-(LED3-B-)") (class "Default")
      (node (ref "LED3") (pin "4") (pinfunction "B-_4") (pintype "unspecified"))
      (node (ref "RN2") (pin "8") (pinfunction "8_8") (pintype "input"))
    )
    (net (code "12") (name "Net-(LED3-G-)") (class "Default")
      (node (ref "LED3") (pin "2") (pinfunction "G-_2") (pintype "unspecified"))
      (node (ref "RN2") (pin "5") (pinfunction "5_5") (pintype "input"))
    )
    (net (code "13") (name "Net-(LED3-R-)") (class "Default")
      (node (ref "LED3") (pin "1") (pinfunction "R-_1") (pintype "unspecified"))
      (node (ref "RN3") (pin "1") (pinfunction "1_1") (pintype "input"))
    )
    (net (code "14") (name "Net-(Q1-B)") (class "Default")
      (node (ref "Q1") (pin "2") (pinfunction "B_2") (pintype "input"))
      (node (ref "RN1") (pin "5") (pinfunction "5_5") (pintype "input"))
    )
    (net (code "15") (name "Net-(Q1-C)") (class "Default")
      (node (ref "Q1") (pin "3") (pinfunction "C_3") (pintype "input"))
      (node (ref "RN1") (pin "6") (pinfunction "6_6") (pintype "input"))
    )
    (net (code "16") (name "Net-(Q2-B)") (class "Default")
      (node (ref "Q2") (pin "2") (pinfunction "B_2") (pintype "input"))
      (node (ref "RN1") (pin "7") (pinfunction "7_7") (pintype "input"))
    )
    (net (code "17") (name "Net-(Q2-C)") (class "Default")
      (node (ref "Q2") (pin "3") (pinfunction "C_3") (pintype "input"))
      (node (ref "RN1") (pin "8") (pinfunction "8_8") (pintype "input"))
    )
    (net (code "18") (name "Net-(Q3-B)") (class "Default")
      (node (ref "Q3") (pin "2") (pinfunction "B_2") (pintype "input"))
      (node (ref "RN2") (pin "3") (pinfunction "3_3") (pintype "input"))
    )
    (net (code "19") (name "Net-(Q3-C)") (class "Default")
      (node (ref "Q3") (pin "3") (pinfunction "C_3") (pintype "input"))
      (node (ref "RN2") (pin "4") (pinfunction "4_4") (pintype "input"))
    )
    (net (code "20") (name "Net-(Q4-B)") (class "Default")
      (node (ref "Q4") (pin "2") (pinfunction "B_2") (pintype "input"))
      (node (ref "RN2") (pin "2") (pinfunction "2_2") (pintype "input"))
    )
    (net (code "21") (name "Net-(Q4-C)") (class "Default")
      (node (ref "Q4") (pin "3") (pinfunction "C_3") (pintype "input"))
      (node (ref "RN2") (pin "1") (pinfunction "1_1") (pintype "input"))
    )
    (net (code "22") (name "Net-(Q5-B)") (class "Default")
      (node (ref "Q5") (pin "2") (pinfunction "B_2") (pintype "input"))
      (node (ref "RN3") (pin "7") (pinfunction "7_7") (pintype "input"))
    )
    (net (code "23") (name "Net-(Q5-C)") (class "Default")
      (node (ref "Q5") (pin "3") (pinfunction "C_3") (pintype "input"))
      (node (ref "RN3") (pin "8") (pinfunction "8_8") (pintype "input"))
    )
    (net (code "24") (name "Net-(Q6-B)") (class "Default")
      (node (ref "Q6") (pin "2") (pinfunction "B_2") (pintype "input"))
      (node (ref "RN3") (pin "3") (pinfunction "3_3") (pintype "input"))
    )
    (net (code "25") (name "Net-(Q6-C)") (class "Default")
      (node (ref "Q6") (pin "3") (pinfunction "C_3") (pintype "input"))
      (node (ref "RN3") (pin "4") (pinfunction "4_4") (pintype "input"))
    )
    (net (code "26") (name "Net-(R1-Pad1)") (class "Default")
      (node (ref "R1") (pin "1") (pinfunction "1_1") (pintype "unspecified"))
      (node (ref "SW4") (pin "6") (pinfunction "6_6") (pintype "input"))
    )
    (net (code "27") (name "Net-(RN1-Pad1)") (class "Default")
      (node (ref "RN1") (pin "1") (pinfunction "1_1") (pintype "input"))
      (node (ref "SYS_STATE1") (pin "2") (pinfunction "2_2") (pintype "unspecified"))
    )
    (net (code "28") (name "Net-(RN1-Pad3)") (class "Default")
      (node (ref "RN1") (pin "3") (pinfunction "3_3") (pintype "input"))
      (node (ref "SYS_STATE2") (pin "2") (pinfunction "2_2") (pintype "unspecified"))
    )
    (net (code "29") (name "Net-(RN4-Pad1)") (class "Default")
      (node (ref "RN4") (pin "1") (pinfunction "1_1") (pintype "input"))
      (node (ref "SW4") (pin "5") (pinfunction "5_5") (pintype "input"))
    )
    (net (code "30") (name "Net-(RN4-Pad2)") (class "Default")
      (node (ref "RN4") (pin "2") (pinfunction "2_2") (pintype "input"))
      (node (ref "SW4") (pin "4") (pinfunction "4_4") (pintype "input"))
    )
    (net (code "31") (name "Net-(RN4-Pad3)") (class "Default")
      (node (ref "RN4") (pin "3") (pinfunction "3_3") (pintype "input"))
      (node (ref "SW4") (pin "3") (pinfunction "3_3") (pintype "input"))
    )
    (net (code "32") (name "Net-(RN4-Pad4)") (class "Default")
      (node (ref "RN4") (pin "4") (pinfunction "4_4") (pintype "input"))
      (node (ref "SW4") (pin "2") (pinfunction "2_2") (pintype "input"))
    )
    (net (code "33") (name "Net-(U1-PD0-OSC_IN)") (class "Default")
      (node (ref "C5") (pin "2") (pinfunction "2_2") (pintype "unspecified"))
      (node (ref "R4") (pin "1") (pinfunction "1_1") (pintype "unspecified"))
      (node (ref "U1") (pin "5") (pinfunction "PD0-OSC_IN_5") (pintype "unspecified"))
      (node (ref "X1") (pin "3") (pinfunction "3_3") (pintype "input"))
    )
    (net (code "34") (name "Net-(U1-PD1-OSC_OUT)") (class "Default")
      (node (ref "C4") (pin "2") (pinfunction "2_2") (pintype "unspecified"))
      (node (ref "R4") (pin "2") (pinfunction "2_2") (pintype "unspecified"))
      (node (ref "U1") (pin "6") (pinfunction "PD1-OSC_OUT_6") (pintype "unspecified"))
      (node (ref "X1") (pin "1") (pinfunction "1_1") (pintype "input"))
    )
    (net (code "35") (name "a0") (class "Default")
      (node (ref "FPC3") (pin "7") (pinfunction "7_7") (pintype "unspecified"))
      (node (ref "U1") (pin "8") (pinfunction "PC0_8") (pintype "unspecified"))
    )
    (net (code "36") (name "a1") (class "Default")
      (node (ref "FPC3") (pin "5") (pinfunction "5_5") (pintype "unspecified"))
      (node (ref "U1") (pin "59") (pinfunction "PB7_59") (pintype "unspecified"))
    )
    (net (code "37") (name "b0") (class "Default")
      (node (ref "FPC3") (pin "6") (pinfunction "6_6") (pintype "unspecified"))
      (node (ref "U1") (pin "9") (pinfunction "PC1_9") (pintype "unspecified"))
    )
    (net (code "38") (name "b1") (class "Default")
      (node (ref "FPC3") (pin "4") (pinfunction "4_4") (pintype "unspecified"))
      (node (ref "U1") (pin "58") (pinfunction "PB6_58") (pintype "unspecified"))
    )
    (net (code "39") (name "batADC") (class "Default")
      (node (ref "R14") (pin "1") (pinfunction "1_1") (pintype "unspecified"))
      (node (ref "R15") (pin "2") (pinfunction "2_2") (pintype "unspecified"))
      (node (ref "U1") (pin "11") (pinfunction "PC3_11") (pintype "unspecified"))
    )
    (net (code "40") (name "beep") (class "Default")
      (node (ref "RN3") (pin "6") (pinfunction "6_6") (pintype "input"))
      (node (ref "U1") (pin "18") (pinfunction "PD4_18") (pintype "unspecified"))
    )
    (net (code "41") (name "blerx") (class "Default")
      (node (ref "SW8") (pin "4") (pinfunction "4_4") (pintype "unspecified"))
      (node (ref "U15") (pin "142") (pinfunction "PE1_142") (pintype "unspecified"))
    )
    (net (code "42") (name "bletx") (class "Default")
      (node (ref "SW8") (pin "1") (pinfunction "1_1") (pintype "unspecified"))
      (node (ref "U15") (pin "141") (pinfunction "PE0_141") (pintype "unspecified"))
    )
    (net (code "43") (name "camera_data0") (class "Default")
      (node (ref "FPC1") (pin "8") (pinfunction "8_8") (pintype "unspecified"))
      (node (ref "U15") (pin "34") (pinfunction "WKP0_PA0_34") (pintype "unspecified"))
    )
    (net (code "44") (name "camera_data1") (class "Default")
      (node (ref "FPC1") (pin "9") (pinfunction "9_9") (pintype "unspecified"))
      (node (ref "U15") (pin "35") (pinfunction "PA1_35") (pintype "unspecified"))
    )
    (net (code "45") (name "camera_data2") (class "Default")
      (node (ref "FPC1") (pin "10") (pinfunction "10_10") (pintype "unspecified"))
      (node (ref "U15") (pin "36") (pinfunction "WKP2_PA2_36") (pintype "unspecified"))
    )
    (net (code "46") (name "camera_data3") (class "Default")
      (node (ref "FPC1") (pin "11") (pinfunction "11_11") (pintype "unspecified"))
      (node (ref "U15") (pin "37") (pinfunction "PA3_37") (pintype "unspecified"))
    )
    (net (code "47") (name "camera_data4") (class "Default")
      (node (ref "FPC1") (pin "12") (pinfunction "12_12") (pintype "unspecified"))
      (node (ref "U15") (pin "40") (pinfunction "PA4_40") (pintype "unspecified"))
    )
    (net (code "48") (name "camera_data5") (class "Default")
      (node (ref "FPC1") (pin "13") (pinfunction "13_13") (pintype "unspecified"))
      (node (ref "U15") (pin "41") (pinfunction "PA5_41") (pintype "unspecified"))
    )
    (net (code "49") (name "camera_data6") (class "Default")
      (node (ref "FPC1") (pin "14") (pinfunction "14_14") (pintype "unspecified"))
      (node (ref "U15") (pin "42") (pinfunction "PA6_42") (pintype "unspecified"))
    )
    (net (code "50") (name "camera_data7") (class "Default")
      (node (ref "FPC1") (pin "15") (pinfunction "15_15") (pintype "unspecified"))
      (node (ref "U15") (pin "43") (pinfunction "PA7_43") (pintype "unspecified"))
    )
    (net (code "51") (name "camera_rx") (class "Default")
      (node (ref "FPC1") (pin "4") (pinfunction "4_4") (pintype "unspecified"))
      (node (ref "U15") (pin "59") (pinfunction "PE8_59") (pintype "unspecified"))
    )
    (net (code "52") (name "camera_tx") (class "Default")
      (node (ref "FPC1") (pin "3") (pinfunction "3_3") (pintype "unspecified"))
      (node (ref "U15") (pin "58") (pinfunction "PE7_58") (pintype "unspecified"))
    )
    (net (code "53") (name "com_rx") (class "Default")
      (node (ref "FPC3") (pin "2") (pinfunction "2_2") (pintype "unspecified"))
      (node (ref "SW8") (pin "5") (pinfunction "5_5") (pintype "unspecified"))
    )
    (net (code "54") (name "com_tx") (class "Default")
      (node (ref "FPC3") (pin "1") (pinfunction "1_1") (pintype "unspecified"))
      (node (ref "SW8") (pin "2") (pinfunction "2_2") (pintype "unspecified"))
    )
    (net (code "55") (name "dat0") (class "Default")
      (node (ref "U1") (pin "14") (pinfunction "PA0-WKUP_14") (pintype "unspecified"))
      (node (ref "U15") (pin "10") (pinfunction "PF0_10") (pintype "unspecified"))
    )
    (net (code "56") (name "dat1") (class "Default")
      (node (ref "U1") (pin "15") (pinfunction "PA1_15") (pintype "unspecified"))
      (node (ref "U15") (pin "11") (pinfunction "PF1_11") (pintype "unspecified"))
    )
    (net (code "57") (name "dat2") (class "Default")
      (node (ref "U1") (pin "16") (pinfunction "PA2_16") (pintype "unspecified"))
      (node (ref "U15") (pin "12") (pinfunction "PF2_12") (pintype "unspecified"))
    )
    (net (code "58") (name "dat3") (class "Default")
      (node (ref "U1") (pin "17") (pinfunction "PA3_17") (pintype "unspecified"))
      (node (ref "U15") (pin "13") (pinfunction "PF3_13") (pintype "unspecified"))
    )
    (net (code "59") (name "dat4") (class "Default")
      (node (ref "U1") (pin "20") (pinfunction "PA4_20") (pintype "unspecified"))
      (node (ref "U15") (pin "14") (pinfunction "PF4_14") (pintype "unspecified"))
    )
    (net (code "60") (name "dat5") (class "Default")
      (node (ref "U1") (pin "21") (pinfunction "PA5_21") (pintype "unspecified"))
      (node (ref "U15") (pin "15") (pinfunction "PF5_15") (pintype "unspecified"))
    )
    (net (code "61") (name "dat6") (class "Default")
      (node (ref "U1") (pin "22") (pinfunction "PA6_22") (pintype "unspecified"))
      (node (ref "U15") (pin "18") (pinfunction "PF6_18") (pintype "unspecified"))
    )
    (net (code "62") (name "dat7") (class "Default")
      (node (ref "U1") (pin "23") (pinfunction "PA7_23") (pintype "unspecified"))
      (node (ref "U15") (pin "19") (pinfunction "PF7_19") (pintype "unspecified"))
    )
    (net (code "63") (name "dat8") (class "Default")
      (node (ref "U1") (pin "41") (pinfunction "PA8_41") (pintype "unspecified"))
      (node (ref "U15") (pin "20") (pinfunction "PF8_20") (pintype "unspecified"))
    )
    (net (code "64") (name "dat9") (class "Default")
      (node (ref "U1") (pin "42") (pinfunction "PA9_42") (pintype "unspecified"))
      (node (ref "U15") (pin "21") (pinfunction "PF9_21") (pintype "unspecified"))
    )
    (net (code "65") (name "dat10") (class "Default")
      (node (ref "U1") (pin "43") (pinfunction "PA10_43") (pintype "unspecified"))
      (node (ref "U15") (pin "22") (pinfunction "PF10_22") (pintype "unspecified"))
    )
    (net (code "66") (name "dat11") (class "Default")
      (node (ref "U1") (pin "44") (pinfunction "PA11_44") (pintype "unspecified"))
      (node (ref "U15") (pin "49") (pinfunction "PF11_49") (pintype "unspecified"))
    )
    (net (code "67") (name "dat12") (class "Default")
      (node (ref "U1") (pin "45") (pinfunction "PA12_45") (pintype "unspecified"))
      (node (ref "U15") (pin "50") (pinfunction "PF12_50") (pintype "unspecified"))
    )
    (net (code "68") (name "dat13") (class "Default")
      (node (ref "J1") (pin "3") (pinfunction "3_3") (pintype "unspecified"))
      (node (ref "U1") (pin "46") (pinfunction "PA13_46") (pintype "unspecified"))
      (node (ref "U15") (pin "53") (pinfunction "PF13_53") (pintype "unspecified"))
    )
    (net (code "69") (name "dat14") (class "Default")
      (node (ref "J1") (pin "4") (pinfunction "4_4") (pintype "unspecified"))
      (node (ref "U1") (pin "49") (pinfunction "PA14_49") (pintype "unspecified"))
      (node (ref "U15") (pin "54") (pinfunction "PF14_54") (pintype "unspecified"))
    )
    (net (code "70") (name "dat15") (class "Default")
      (node (ref "U1") (pin "50") (pinfunction "PA15_50") (pintype "unspecified"))
      (node (ref "U15") (pin "55") (pinfunction "PF15_55") (pintype "unspecified"))
    )
    (net (code "71") (name "flash_CS") (class "Default")
      (node (ref "R29") (pin "1") (pinfunction "1_1") (pintype "unspecified"))
      (node (ref "U1") (pin "47") (pinfunction "PD2_47") (pintype "unspecified"))
      (node (ref "U12") (pin "1") (pinfunction "CS#_1") (pintype "unspecified"))
    )
    (net (code "72") (name "hc244oe") (class "Default")
      (node (ref "U1") (pin "48") (pinfunction "PD3_48") (pintype "unspecified"))
      (node (ref "U14") (pin "1") (pinfunction "1OE#_1") (pintype "unspecified"))
    )
    (net (code "73") (name "href") (class "Default")
      (node (ref "FPC1") (pin "5") (pinfunction "5_5") (pintype "unspecified"))
      (node (ref "U15") (pin "44") (pinfunction "PC4_44") (pintype "unspecified"))
    )
    (net (code "74") (name "ips_bk") (class "Default")
      (node (ref "IPS") (pin "8") (pinfunction "8_8") (pintype "unspecified"))
      (node (ref "U15") (pin "136") (pinfunction "PB6_136") (pintype "unspecified"))
    )
    (net (code "75") (name "ips_cs") (class "Default")
      (node (ref "IPS") (pin "7") (pinfunction "7_7") (pintype "unspecified"))
      (node (ref "U15") (pin "139") (pinfunction "PB8_139") (pintype "unspecified"))
    )
    (net (code "76") (name "ips_dc") (class "Default")
      (node (ref "IPS") (pin "6") (pinfunction "6_6") (pintype "unspecified"))
      (node (ref "U15") (pin "137") (pinfunction "PB7_137") (pintype "unspecified"))
    )
    (net (code "77") (name "ips_reset") (class "Default")
      (node (ref "IPS") (pin "5") (pinfunction "5_5") (pintype "unspecified"))
      (node (ref "U15") (pin "140") (pinfunction "PB9_140") (pintype "unspecified"))
    )
    (net (code "78") (name "key_down") (class "Default")
      (node (ref "C17") (pin "2") (pinfunction "2_2") (pintype "unspecified"))
      (node (ref "RN4") (pin "7") (pinfunction "7_7") (pintype "input"))
      (node (ref "U1") (pin "52") (pinfunction "PC11_52") (pintype "unspecified"))
    )
    (net (code "79") (name "key_left") (class "Default")
      (node (ref "C7") (pin "1") (pinfunction "1_1") (pintype "unspecified"))
      (node (ref "RN4") (pin "5") (pinfunction "5_5") (pintype "input"))
      (node (ref "U1") (pin "56") (pinfunction "PB4_56") (pintype "unspecified"))
    )
    (net (code "80") (name "key_mid") (class "Default")
      (node (ref "C16") (pin "1") (pinfunction "1_1") (pintype "unspecified"))
      (node (ref "RN4") (pin "6") (pinfunction "6_6") (pintype "input"))
      (node (ref "U1") (pin "53") (pinfunction "PC12_53") (pintype "unspecified"))
    )
    (net (code "81") (name "key_right") (class "Default")
      (node (ref "C6") (pin "2") (pinfunction "2_2") (pintype "unspecified"))
      (node (ref "RN4") (pin "8") (pinfunction "8_8") (pintype "input"))
      (node (ref "U1") (pin "55") (pinfunction "PB3_55") (pintype "unspecified"))
    )
    (net (code "82") (name "key_up") (class "Default")
      (node (ref "C1") (pin "2") (pinfunction "2_2") (pintype "unspecified"))
      (node (ref "R1") (pin "2") (pinfunction "2_2") (pintype "unspecified"))
      (node (ref "U1") (pin "54") (pinfunction "PD6_54") (pintype "unspecified"))
    )
    (net (code "83") (name "led") (class "Default")
      (node (ref "RN1") (pin "2") (pinfunction "2_2") (pintype "input"))
      (node (ref "U1") (pin "27") (pinfunction "PB1_27") (pintype "unspecified"))
    )
    (net (code "84") (name "led3277") (class "Default")
      (node (ref "RN1") (pin "4") (pinfunction "4_4") (pintype "input"))
      (node (ref "U15") (pin "47") (pinfunction "PB1_47") (pintype "unspecified"))
    )
    (net (code "85") (name "m_request") (class "Default")
      (node (ref "U1") (pin "2") (pinfunction "PC13_2") (pintype "unspecified"))
      (node (ref "U15") (pin "26") (pinfunction "PC0_26") (pintype "unspecified"))
    )
    (net (code "86") (name "miso") (class "Default")
      (node (ref "U1") (pin "33") (pinfunction "PB12_33") (pintype "unspecified"))
      (node (ref "U12") (pin "2") (pinfunction "DO(IO1)_2") (pintype "unspecified"))
    )
    (net (code "87") (name "mosi") (class "Default")
      (node (ref "SCREEN1") (pin "4") (pinfunction "4_4") (pintype "input"))
      (node (ref "U1") (pin "34") (pinfunction "PB13_34") (pintype "unspecified"))
      (node (ref "U12") (pin "5") (pinfunction "DI(IO0)_5") (pintype "unspecified"))
    )
    (net (code "88") (name "motor0") (class "Default")
      (node (ref "U1") (pin "37") (pinfunction "PC6_37") (pintype "unspecified"))
      (node (ref "U14") (pin "2") (pinfunction "1A0_2") (pintype "unspecified"))
    )
    (net (code "89") (name "motor1") (class "Default")
      (node (ref "U1") (pin "38") (pinfunction "PC7_38") (pintype "unspecified"))
      (node (ref "U14") (pin "4") (pinfunction "1A1_4") (pintype "unspecified"))
    )
    (net (code "90") (name "motor2") (class "Default")
      (node (ref "U1") (pin "39") (pinfunction "PC8_39") (pintype "unspecified"))
      (node (ref "U14") (pin "6") (pinfunction "1A2_6") (pintype "unspecified"))
    )
    (net (code "91") (name "motor3") (class "Default")
      (node (ref "U1") (pin "40") (pinfunction "PC9_40") (pintype "unspecified"))
      (node (ref "U14") (pin "8") (pinfunction "1A3_8") (pintype "unspecified"))
    )
    (net (code "92") (name "mpuInt") (class "Default")
      (node (ref "FPC2") (pin "2") (pinfunction "2_2") (pintype "unspecified"))
      (node (ref "U1") (pin "19") (pinfunction "PD5_19") (pintype "unspecified"))
    )
    (net (code "93") (name "pclk") (class "Default")
      (node (ref "FPC1") (pin "1") (pinfunction "1_1") (pintype "unspecified"))
      (node (ref "U15") (pin "46") (pinfunction "PB0_46") (pintype "unspecified"))
    )
    (net (code "94") (name "pwm1") (class "Default")
      (node (ref "FPC3") (pin "9") (pinfunction "9_9") (pintype "unspecified"))
      (node (ref "U14") (pin "18") (pinfunction "1Y0_18") (pintype "unspecified"))
    )
    (net (code "95") (name "pwm2") (class "Default")
      (node (ref "FPC3") (pin "10") (pinfunction "10_10") (pintype "unspecified"))
      (node (ref "U14") (pin "16") (pinfunction "1Y1_16") (pintype "unspecified"))
    )
    (net (code "96") (name "pwm3") (class "Default")
      (node (ref "FPC3") (pin "11") (pinfunction "11_11") (pintype "unspecified"))
      (node (ref "U14") (pin "14") (pinfunction "1Y2_14") (pintype "unspecified"))
    )
    (net (code "97") (name "pwm4") (class "Default")
      (node (ref "FPC3") (pin "12") (pinfunction "12_12") (pintype "unspecified"))
      (node (ref "U14") (pin "12") (pinfunction "1Y3_12") (pintype "unspecified"))
    )
    (net (code "98") (name "rgb_b") (class "Default")
      (node (ref "RN2") (pin "7") (pinfunction "7_7") (pintype "input"))
      (node (ref "U15") (pin "65") (pinfunction "PE12_65") (pintype "unspecified"))
    )
    (net (code "99") (name "rgb_g") (class "Default")
      (node (ref "RN2") (pin "6") (pinfunction "6_6") (pintype "input"))
      (node (ref "U15") (pin "66") (pinfunction "PE13_66") (pintype "unspecified"))
    )
    (net (code "100") (name "rgb_r") (class "Default")
      (node (ref "RN3") (pin "2") (pinfunction "2_2") (pintype "input"))
      (node (ref "U15") (pin "67") (pinfunction "PE14_67") (pintype "unspecified"))
    )
    (net (code "101") (name "rst") (class "Default")
      (node (ref "C2") (pin "2") (pinfunction "2_2") (pintype "unspecified"))
      (node (ref "R3") (pin "2") (pinfunction "2_2") (pintype "unspecified"))
      (node (ref "SW7") (pin "2") (pinfunction "2_2") (pintype "unspecified"))
      (node (ref "U1") (pin "7") (pinfunction "nRST_7") (pintype "unspecified"))
    )
    (net (code "102") (name "rst3277") (class "Default")
      (node (ref "C3") (pin "2") (pinfunction "2_2") (pintype "unspecified"))
      (node (ref "R2") (pin "2") (pinfunction "2_2") (pintype "unspecified"))
      (node (ref "SW3") (pin "2") (pinfunction "2_2") (pintype "unspecified"))
      (node (ref "U15") (pin "25") (pinfunction "NRST_25") (pintype "unspecified"))
    )
    (net (code "103") (name "s_ok") (class "Default")
      (node (ref "U1") (pin "3") (pinfunction "PC14_3") (pintype "unspecified"))
      (node (ref "U15") (pin "27") (pinfunction "PC1_27") (pintype "unspecified"))
    )
    (net (code "104") (name "scl") (class "Default")
      (node (ref "FPC2") (pin "4") (pinfunction "4_4") (pintype "unspecified"))
      (node (ref "U1") (pin "29") (pinfunction "PB10_29") (pintype "unspecified"))
    )
    (net (code "105") (name "sclk") (class "Default")
      (node (ref "SCREEN1") (pin "3") (pinfunction "3_3") (pintype "input"))
      (node (ref "U1") (pin "35") (pinfunction "PB14_35") (pintype "unspecified"))
      (node (ref "U12") (pin "6") (pinfunction "CLK_6") (pintype "unspecified"))
    )
    (net (code "106") (name "screen_cs") (class "Default")
      (node (ref "SCREEN1") (pin "7") (pinfunction "7_7") (pintype "input"))
      (node (ref "U1") (pin "28") (pinfunction "PB2_28") (pintype "unspecified"))
    )
    (net (code "107") (name "screen_dc") (class "Default")
      (node (ref "SCREEN1") (pin "6") (pinfunction "6_6") (pintype "input"))
      (node (ref "U1") (pin "36") (pinfunction "PB15_36") (pintype "unspecified"))
    )
    (net (code "108") (name "screen_reset") (class "Default")
      (node (ref "SCREEN1") (pin "5") (pinfunction "5_5") (pintype "input"))
      (node (ref "U1") (pin "26") (pinfunction "PB0_26") (pintype "unspecified"))
    )
    (net (code "109") (name "sd_det") (class "Default")
      (node (ref "CARD1") (pin "9") (pinfunction "CD_9") (pintype "unspecified"))
      (node (ref "U15") (pin "100") (pinfunction "PA8_100") (pintype "unspecified"))
    )
    (net (code "110") (name "sda") (class "Default")
      (node (ref "FPC2") (pin "5") (pinfunction "5_5") (pintype "unspecified"))
      (node (ref "U1") (pin "30") (pinfunction "PB11_30") (pintype "unspecified"))
    )
    (net (code "111") (name "sdio_ck") (class "Default")
      (node (ref "CARD1") (pin "5") (pinfunction "CLK_5") (pintype "unspecified"))
      (node (ref "U15") (pin "113") (pinfunction "PC12_113") (pintype "unspecified"))
    )
    (net (code "112") (name "sdio_cmd") (class "Default")
      (node (ref "CARD1") (pin "3") (pinfunction "CMD_3") (pintype "unspecified"))
      (node (ref "U15") (pin "116") (pinfunction "PD2_116") (pintype "unspecified"))
    )
    (net (code "113") (name "sdio_d0") (class "Default")
      (node (ref "CARD1") (pin "7") (pinfunction "DAT0_7") (pintype "unspecified"))
      (node (ref "U15") (pin "98") (pinfunction "PC8_98") (pintype "unspecified"))
    )
    (net (code "114") (name "sdio_d1") (class "Default")
      (node (ref "CARD1") (pin "8") (pinfunction "DAT1_8") (pintype "unspecified"))
      (node (ref "U15") (pin "99") (pinfunction "PC9_99") (pintype "unspecified"))
    )
    (net (code "115") (name "sdio_d2") (class "Default")
      (node (ref "CARD1") (pin "1") (pinfunction "DAT2_1") (pintype "unspecified"))
      (node (ref "U15") (pin "111") (pinfunction "PC10_111") (pintype "unspecified"))
    )
    (net (code "116") (name "sdio_d3") (class "Default")
      (node (ref "CARD1") (pin "2") (pinfunction "CD/DAT3_2") (pintype "unspecified"))
      (node (ref "U15") (pin "112") (pinfunction "PC11_112") (pintype "unspecified"))
    )
    (net (code "117") (name "swd_clk") (class "Default")
      (node (ref "J2") (pin "4") (pinfunction "4_4") (pintype "unspecified"))
      (node (ref "U15") (pin "109") (pinfunction "PA14_109") (pintype "unspecified"))
    )
    (net (code "118") (name "swd_io") (class "Default")
      (node (ref "J2") (pin "3") (pinfunction "3_3") (pintype "unspecified"))
      (node (ref "U15") (pin "105") (pinfunction "PA13_105") (pintype "unspecified"))
    )
    (net (code "119") (name "unconnected-(FPC1-Pad19)") (class "Default")
      (node (ref "FPC1") (pin "19") (pinfunction "19_19") (pintype "unspecified+no_connect"))
    )
    (net (code "120") (name "unconnected-(FPC1-Pad20)") (class "Default")
      (node (ref "FPC1") (pin "20") (pinfunction "20_20") (pintype "unspecified+no_connect"))
    )
    (net (code "121") (name "unconnected-(FPC2-Pad6)") (class "Default")
      (node (ref "FPC2") (pin "6") (pinfunction "6_6") (pintype "unspecified+no_connect"))
    )
    (net (code "122") (name "unconnected-(FPC2-Pad7)") (class "Default")
      (node (ref "FPC2") (pin "7") (pinfunction "7_7") (pintype "unspecified+no_connect"))
    )
    (net (code "123") (name "unconnected-(FPC3-Pad13)") (class "Default")
      (node (ref "FPC3") (pin "13") (pinfunction "13_13") (pintype "unspecified+no_connect"))
    )
    (net (code "124") (name "unconnected-(FPC3-Pad14)") (class "Default")
      (node (ref "FPC3") (pin "14") (pinfunction "14_14") (pintype "unspecified+no_connect"))
    )
    (net (code "125") (name "unconnected-(SW1-Pad1)") (class "Default")
      (node (ref "SW1") (pin "1") (pinfunction "1_1") (pintype "unspecified+no_connect"))
    )
    (net (code "126") (name "unconnected-(U1-PB8-Pad61)") (class "Default")
      (node (ref "U1") (pin "61") (pinfunction "PB8_61") (pintype "unspecified+no_connect"))
    )
    (net (code "127") (name "unconnected-(U1-PB9-Pad62)") (class "Default")
      (node (ref "U1") (pin "62") (pinfunction "PB9_62") (pintype "unspecified+no_connect"))
    )
    (net (code "128") (name "unconnected-(U1-PC2-Pad10)") (class "Default")
      (node (ref "U1") (pin "10") (pinfunction "PC2_10") (pintype "unspecified+no_connect"))
    )
    (net (code "129") (name "unconnected-(U1-PC10-Pad51)") (class "Default")
      (node (ref "U1") (pin "51") (pinfunction "PC10_51") (pintype "unspecified+no_connect"))
    )
    (net (code "130") (name "unconnected-(U1-PC15-Pad4)") (class "Default")
      (node (ref "U1") (pin "4") (pinfunction "PC15_4") (pintype "unspecified+no_connect"))
    )
    (net (code "131") (name "unconnected-(U1-PD7-Pad1)") (class "Default")
      (node (ref "U1") (pin "1") (pinfunction "PD7_1") (pintype "unspecified+no_connect"))
    )
    (net (code "132") (name "unconnected-(U14-2A0-Pad17)") (class "Default")
      (node (ref "U14") (pin "17") (pinfunction "2A0_17") (pintype "unspecified+no_connect"))
    )
    (net (code "133") (name "unconnected-(U14-2A1-Pad15)") (class "Default")
      (node (ref "U14") (pin "15") (pinfunction "2A1_15") (pintype "unspecified+no_connect"))
    )
    (net (code "134") (name "unconnected-(U14-2A2-Pad13)") (class "Default")
      (node (ref "U14") (pin "13") (pinfunction "2A2_13") (pintype "unspecified+no_connect"))
    )
    (net (code "135") (name "unconnected-(U14-2A3-Pad11)") (class "Default")
      (node (ref "U14") (pin "11") (pinfunction "2A3_11") (pintype "unspecified+no_connect"))
    )
    (net (code "136") (name "unconnected-(U14-2OE#-Pad19)") (class "Default")
      (node (ref "U14") (pin "19") (pinfunction "2OE#_19") (pintype "unspecified+no_connect"))
    )
    (net (code "137") (name "unconnected-(U14-2Y0-Pad3)") (class "Default")
      (node (ref "U14") (pin "3") (pinfunction "2Y0_3") (pintype "unspecified+no_connect"))
    )
    (net (code "138") (name "unconnected-(U14-2Y1-Pad5)") (class "Default")
      (node (ref "U14") (pin "5") (pinfunction "2Y1_5") (pintype "unspecified+no_connect"))
    )
    (net (code "139") (name "unconnected-(U14-2Y2-Pad7)") (class "Default")
      (node (ref "U14") (pin "7") (pinfunction "2Y2_7") (pintype "unspecified+no_connect"))
    )
    (net (code "140") (name "unconnected-(U14-2Y3-Pad9)") (class "Default")
      (node (ref "U14") (pin "9") (pinfunction "2Y3_9") (pintype "unspecified+no_connect"))
    )
    (net (code "141") (name "unconnected-(U15-PA9_USB_VBUS-Pad101)") (class "Default")
      (node (ref "U15") (pin "101") (pinfunction "PA9_USB_VBUS_101") (pintype "unspecified+no_connect"))
    )
    (net (code "142") (name "unconnected-(U15-PA10_USB_ID-Pad102)") (class "Default")
      (node (ref "U15") (pin "102") (pinfunction "PA10_USB_ID_102") (pintype "unspecified+no_connect"))
    )
    (net (code "143") (name "unconnected-(U15-PA11_USBDM-Pad103)") (class "Default")
      (node (ref "U15") (pin "103") (pinfunction "PA11_USBDM_103") (pintype "unspecified+no_connect"))
    )
    (net (code "144") (name "unconnected-(U15-PA12_USBDP-Pad104)") (class "Default")
      (node (ref "U15") (pin "104") (pinfunction "PA12_USBDP_104") (pintype "unspecified+no_connect"))
    )
    (net (code "145") (name "unconnected-(U15-PA15-Pad110)") (class "Default")
      (node (ref "U15") (pin "110") (pinfunction "PA15_110") (pintype "unspecified+no_connect"))
    )
    (net (code "146") (name "unconnected-(U15-PB4-Pad134)") (class "Default")
      (node (ref "U15") (pin "134") (pinfunction "PB4_134") (pintype "unspecified+no_connect"))
    )
    (net (code "147") (name "unconnected-(U15-PB10-Pad69)") (class "Default")
      (node (ref "U15") (pin "69") (pinfunction "PB10_69") (pintype "unspecified+no_connect"))
    )
    (net (code "148") (name "unconnected-(U15-PB11-Pad70)") (class "Default")
      (node (ref "U15") (pin "70") (pinfunction "PB11_70") (pintype "unspecified+no_connect"))
    )
    (net (code "149") (name "unconnected-(U15-PB12-Pad73)") (class "Default")
      (node (ref "U15") (pin "73") (pinfunction "PB12_73") (pintype "unspecified+no_connect"))
    )
    (net (code "150") (name "unconnected-(U15-PB13-Pad74)") (class "Default")
      (node (ref "U15") (pin "74") (pinfunction "PB13_74") (pintype "unspecified+no_connect"))
    )
    (net (code "151") (name "unconnected-(U15-PB14-Pad75)") (class "Default")
      (node (ref "U15") (pin "75") (pinfunction "PB14_75") (pintype "unspecified+no_connect"))
    )
    (net (code "152") (name "unconnected-(U15-PB15_WKP5-Pad76)") (class "Default")
      (node (ref "U15") (pin "76") (pinfunction "PB15_WKP5_76") (pintype "unspecified+no_connect"))
    )
    (net (code "153") (name "unconnected-(U15-PC2-Pad28)") (class "Default")
      (node (ref "U15") (pin "28") (pinfunction "PC2_28") (pintype "unspecified+no_connect"))
    )
    (net (code "154") (name "unconnected-(U15-PC3-Pad29)") (class "Default")
      (node (ref "U15") (pin "29") (pinfunction "PC3_29") (pintype "unspecified+no_connect"))
    )
    (net (code "155") (name "unconnected-(U15-PC6-Pad96)") (class "Default")
      (node (ref "U15") (pin "96") (pinfunction "PC6_96") (pintype "unspecified+no_connect"))
    )
    (net (code "156") (name "unconnected-(U15-PC7-Pad97)") (class "Default")
      (node (ref "U15") (pin "97") (pinfunction "PC7_97") (pintype "unspecified+no_connect"))
    )
    (net (code "157") (name "unconnected-(U15-PC13_TAMP_RTC_WKP1-Pad7)") (class "Default")
      (node (ref "U15") (pin "7") (pinfunction "PC13_TAMP_RTC_WKP1_7") (pintype "unspecified+no_connect"))
    )
    (net (code "158") (name "unconnected-(U15-PC14-OSC32IN-Pad8)") (class "Default")
      (node (ref "U15") (pin "8") (pinfunction "PC14-OSC32IN_8") (pintype "unspecified+no_connect"))
    )
    (net (code "159") (name "unconnected-(U15-PC15-OSC32OUT-Pad9)") (class "Default")
      (node (ref "U15") (pin "9") (pinfunction "PC15-OSC32OUT_9") (pintype "unspecified+no_connect"))
    )
    (net (code "160") (name "unconnected-(U15-PD0-Pad114)") (class "Default")
      (node (ref "U15") (pin "114") (pinfunction "PD0_114") (pintype "unspecified+no_connect"))
    )
    (net (code "161") (name "unconnected-(U15-PD1-Pad115)") (class "Default")
      (node (ref "U15") (pin "115") (pinfunction "PD1_115") (pintype "unspecified+no_connect"))
    )
    (net (code "162") (name "unconnected-(U15-PD3-Pad117)") (class "Default")
      (node (ref "U15") (pin "117") (pinfunction "PD3_117") (pintype "unspecified+no_connect"))
    )
    (net (code "163") (name "unconnected-(U15-PD4-Pad118)") (class "Default")
      (node (ref "U15") (pin "118") (pinfunction "PD4_118") (pintype "unspecified+no_connect"))
    )
    (net (code "164") (name "unconnected-(U15-PD5-Pad119)") (class "Default")
      (node (ref "U15") (pin "119") (pinfunction "PD5_119") (pintype "unspecified+no_connect"))
    )
    (net (code "165") (name "unconnected-(U15-PD6-Pad122)") (class "Default")
      (node (ref "U15") (pin "122") (pinfunction "PD6_122") (pintype "unspecified+no_connect"))
    )
    (net (code "166") (name "unconnected-(U15-PD7-Pad123)") (class "Default")
      (node (ref "U15") (pin "123") (pinfunction "PD7_123") (pintype "unspecified+no_connect"))
    )
    (net (code "167") (name "unconnected-(U15-PD8-Pad77)") (class "Default")
      (node (ref "U15") (pin "77") (pinfunction "PD8_77") (pintype "unspecified+no_connect"))
    )
    (net (code "168") (name "unconnected-(U15-PD9-Pad78)") (class "Default")
      (node (ref "U15") (pin "78") (pinfunction "PD9_78") (pintype "unspecified+no_connect"))
    )
    (net (code "169") (name "unconnected-(U15-PD10-Pad79)") (class "Default")
      (node (ref "U15") (pin "79") (pinfunction "PD10_79") (pintype "unspecified+no_connect"))
    )
    (net (code "170") (name "unconnected-(U15-PD11-Pad80)") (class "Default")
      (node (ref "U15") (pin "80") (pinfunction "PD11_80") (pintype "unspecified+no_connect"))
    )
    (net (code "171") (name "unconnected-(U15-PD12-Pad81)") (class "Default")
      (node (ref "U15") (pin "81") (pinfunction "PD12_81") (pintype "unspecified+no_connect"))
    )
    (net (code "172") (name "unconnected-(U15-PD13-Pad82)") (class "Default")
      (node (ref "U15") (pin "82") (pinfunction "PD13_82") (pintype "unspecified+no_connect"))
    )
    (net (code "173") (name "unconnected-(U15-PD14-Pad85)") (class "Default")
      (node (ref "U15") (pin "85") (pinfunction "PD14_85") (pintype "unspecified+no_connect"))
    )
    (net (code "174") (name "unconnected-(U15-PD15-Pad86)") (class "Default")
      (node (ref "U15") (pin "86") (pinfunction "PD15_86") (pintype "unspecified+no_connect"))
    )
    (net (code "175") (name "unconnected-(U15-PE2-Pad1)") (class "Default")
      (node (ref "U15") (pin "1") (pinfunction "PE2_1") (pintype "unspecified+no_connect"))
    )
    (net (code "176") (name "unconnected-(U15-PE3-Pad2)") (class "Default")
      (node (ref "U15") (pin "2") (pinfunction "PE3_2") (pintype "unspecified+no_connect"))
    )
    (net (code "177") (name "unconnected-(U15-PE4-Pad3)") (class "Default")
      (node (ref "U15") (pin "3") (pinfunction "PE4_3") (pintype "unspecified+no_connect"))
    )
    (net (code "178") (name "unconnected-(U15-PE5-Pad4)") (class "Default")
      (node (ref "U15") (pin "4") (pinfunction "PE5_4") (pintype "unspecified+no_connect"))
    )
    (net (code "179") (name "unconnected-(U15-PE6-Pad5)") (class "Default")
      (node (ref "U15") (pin "5") (pinfunction "PE6_5") (pintype "unspecified+no_connect"))
    )
    (net (code "180") (name "unconnected-(U15-PE9-Pad60)") (class "Default")
      (node (ref "U15") (pin "60") (pinfunction "PE9_60") (pintype "unspecified+no_connect"))
    )
    (net (code "181") (name "unconnected-(U15-PE10-Pad63)") (class "Default")
      (node (ref "U15") (pin "63") (pinfunction "PE10_63") (pintype "unspecified+no_connect"))
    )
    (net (code "182") (name "unconnected-(U15-PE11-Pad64)") (class "Default")
      (node (ref "U15") (pin "64") (pinfunction "PE11_64") (pintype "unspecified+no_connect"))
    )
    (net (code "183") (name "unconnected-(U15-PE15-Pad68)") (class "Default")
      (node (ref "U15") (pin "68") (pinfunction "PE15_68") (pintype "unspecified+no_connect"))
    )
    (net (code "184") (name "unconnected-(U15-PG0-Pad56)") (class "Default")
      (node (ref "U15") (pin "56") (pinfunction "PG0_56") (pintype "unspecified+no_connect"))
    )
    (net (code "185") (name "unconnected-(U15-PG1-Pad57)") (class "Default")
      (node (ref "U15") (pin "57") (pinfunction "PG1_57") (pintype "unspecified+no_connect"))
    )
    (net (code "186") (name "unconnected-(U15-PG2-Pad87)") (class "Default")
      (node (ref "U15") (pin "87") (pinfunction "PG2_87") (pintype "unspecified+no_connect"))
    )
    (net (code "187") (name "unconnected-(U15-PG3-Pad88)") (class "Default")
      (node (ref "U15") (pin "88") (pinfunction "PG3_88") (pintype "unspecified+no_connect"))
    )
    (net (code "188") (name "unconnected-(U15-PG4-Pad89)") (class "Default")
      (node (ref "U15") (pin "89") (pinfunction "PG4_89") (pintype "unspecified+no_connect"))
    )
    (net (code "189") (name "unconnected-(U15-PG5-Pad90)") (class "Default")
      (node (ref "U15") (pin "90") (pinfunction "PG5_90") (pintype "unspecified+no_connect"))
    )
    (net (code "190") (name "unconnected-(U15-PG6-Pad91)") (class "Default")
      (node (ref "U15") (pin "91") (pinfunction "PG6_91") (pintype "unspecified+no_connect"))
    )
    (net (code "191") (name "unconnected-(U15-PG7-Pad92)") (class "Default")
      (node (ref "U15") (pin "92") (pinfunction "PG7_92") (pintype "unspecified+no_connect"))
    )
    (net (code "192") (name "unconnected-(U15-PG8-Pad93)") (class "Default")
      (node (ref "U15") (pin "93") (pinfunction "PG8_93") (pintype "unspecified+no_connect"))
    )
    (net (code "193") (name "unconnected-(U15-PG9-Pad124)") (class "Default")
      (node (ref "U15") (pin "124") (pinfunction "PG9_124") (pintype "unspecified+no_connect"))
    )
    (net (code "194") (name "unconnected-(U15-PG10-Pad125)") (class "Default")
      (node (ref "U15") (pin "125") (pinfunction "PG10_125") (pintype "unspecified+no_connect"))
    )
    (net (code "195") (name "unconnected-(U15-PG11-Pad126)") (class "Default")
      (node (ref "U15") (pin "126") (pinfunction "PG11_126") (pintype "unspecified+no_connect"))
    )
    (net (code "196") (name "unconnected-(U15-PG12-Pad127)") (class "Default")
      (node (ref "U15") (pin "127") (pinfunction "PG12_127") (pintype "unspecified+no_connect"))
    )
    (net (code "197") (name "unconnected-(U15-PG13-Pad128)") (class "Default")
      (node (ref "U15") (pin "128") (pinfunction "PG13_128") (pintype "unspecified+no_connect"))
    )
    (net (code "198") (name "unconnected-(U15-PG14-Pad129)") (class "Default")
      (node (ref "U15") (pin "129") (pinfunction "PG14_129") (pintype "unspecified+no_connect"))
    )
    (net (code "199") (name "unconnected-(U15-PG15-Pad132)") (class "Default")
      (node (ref "U15") (pin "132") (pinfunction "PG15_132") (pintype "unspecified+no_connect"))
    )
    (net (code "200") (name "unconnected-(U15-PH2-Pad106)") (class "Default")
      (node (ref "U15") (pin "106") (pinfunction "PH2_106") (pintype "unspecified+no_connect"))
    )
    (net (code "201") (name "v12_E") (class "Default")
      (node (ref "FPC3") (pin "8") (pinfunction "8_8") (pintype "unspecified"))
      (node (ref "U1") (pin "57") (pinfunction "PB5_57") (pintype "unspecified"))
    )
    (net (code "202") (name "vsync") (class "Default")
      (node (ref "FPC1") (pin "6") (pinfunction "6_6") (pintype "unspecified"))
      (node (ref "U15") (pin "45") (pinfunction "WKP3_PC5_45") (pintype "unspecified"))
    )
    (net (code "203") (name "xi") (class "Default")
      (node (ref "C9") (pin "2") (pinfunction "2_2") (pintype "unspecified"))
      (node (ref "R32") (pin "1") (pinfunction "1_1") (pintype "unspecified"))
      (node (ref "U15") (pin "23") (pinfunction "PH0-OSC_IN_23") (pintype "unspecified"))
      (node (ref "X2") (pin "1") (pinfunction "1_1") (pintype "input"))
    )
    (net (code "204") (name "xo") (class "Default")
      (node (ref "C8") (pin "2") (pinfunction "2_2") (pintype "unspecified"))
      (node (ref "R32") (pin "2") (pinfunction "2_2") (pintype "unspecified"))
      (node (ref "U15") (pin "24") (pinfunction "PH1-OSC_OUT_24") (pintype "unspecified"))
      (node (ref "X2") (pin "3") (pinfunction "3_3") (pintype "input"))
    )
  )
)
